# StairMastersPDB.net
KiCad netlist of a schematic drawn in Altium Designer
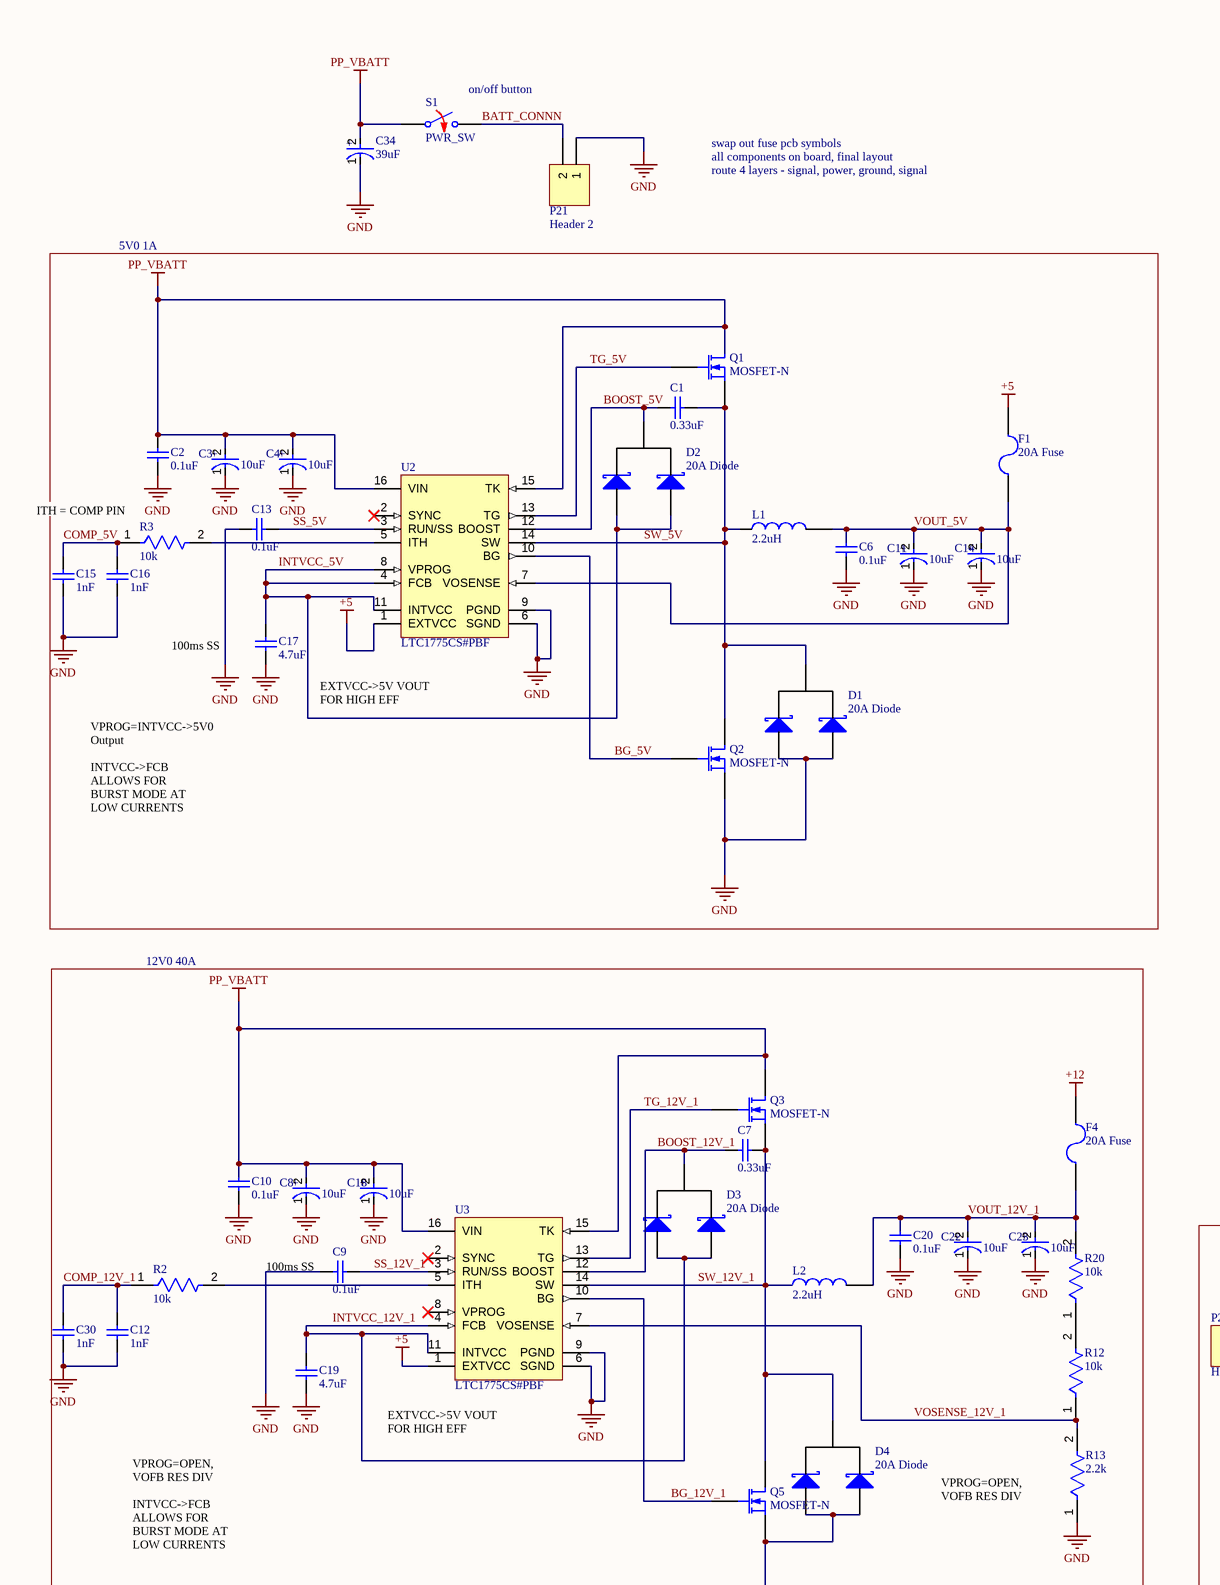
[diagram p0: StairMastersPDB.SchDoc, top left]
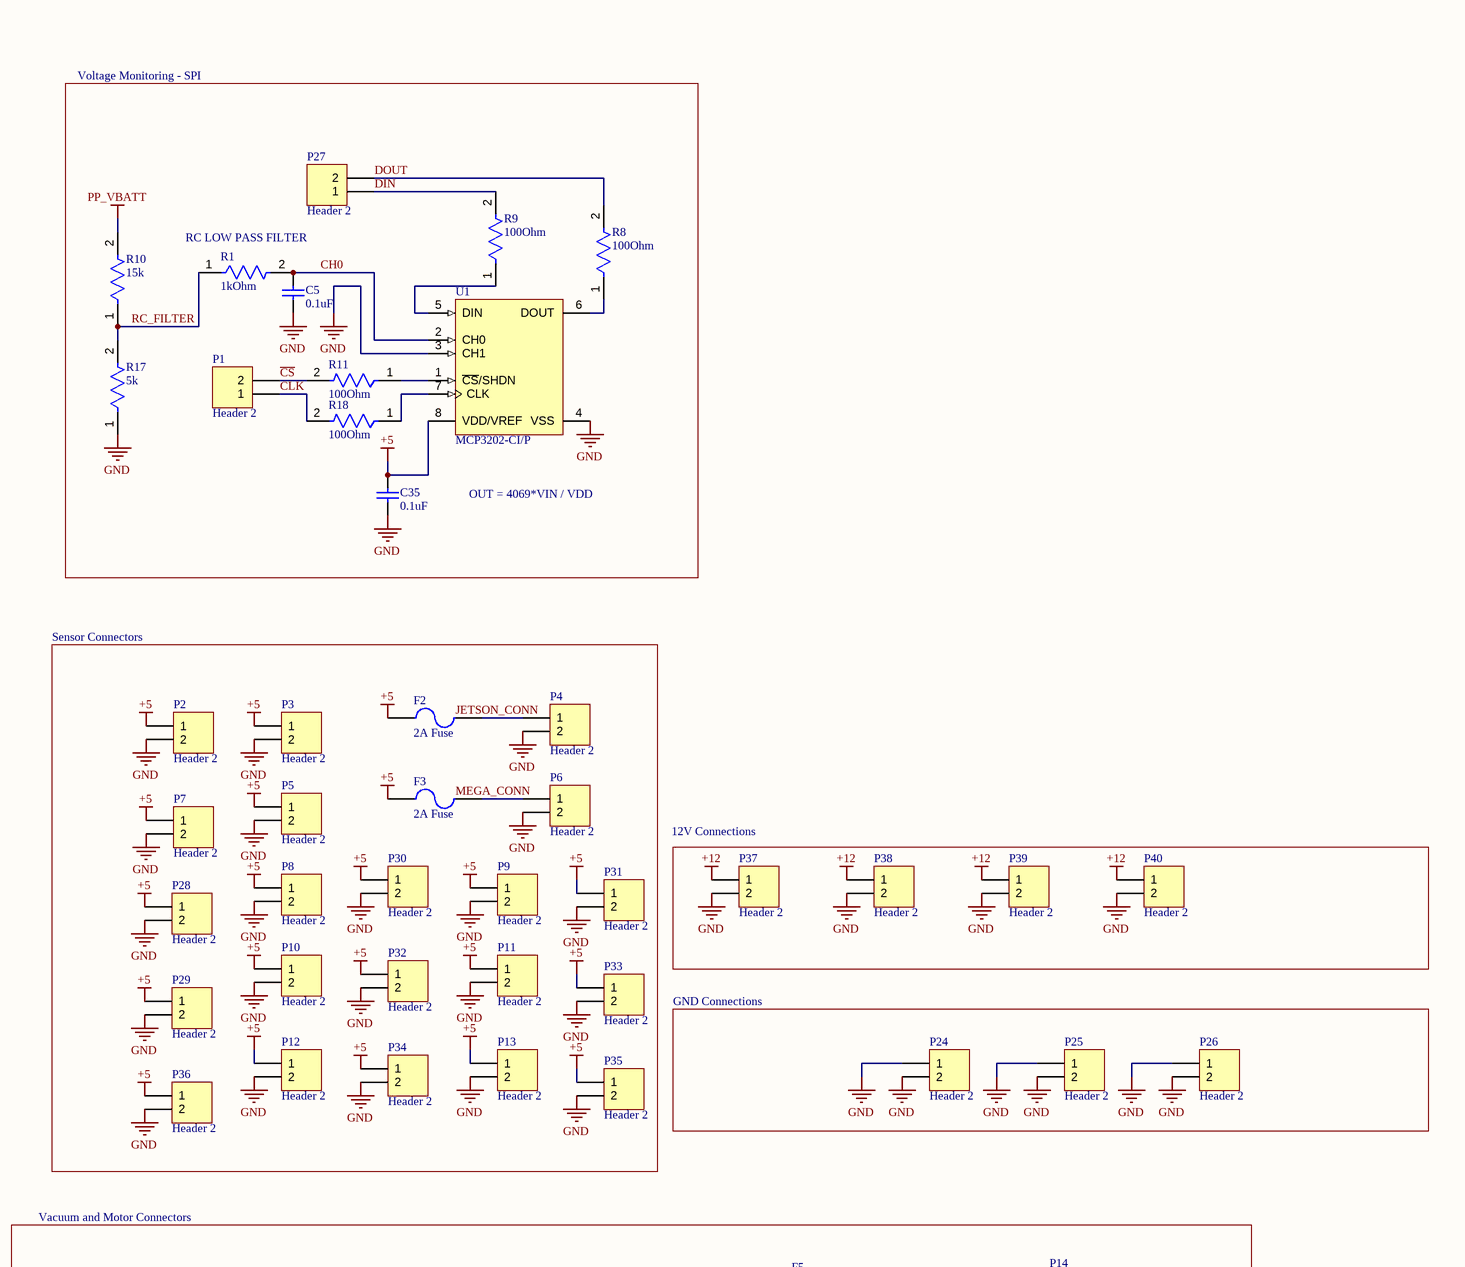
[diagram p1: StairMastersPDB.SchDoc, top right]
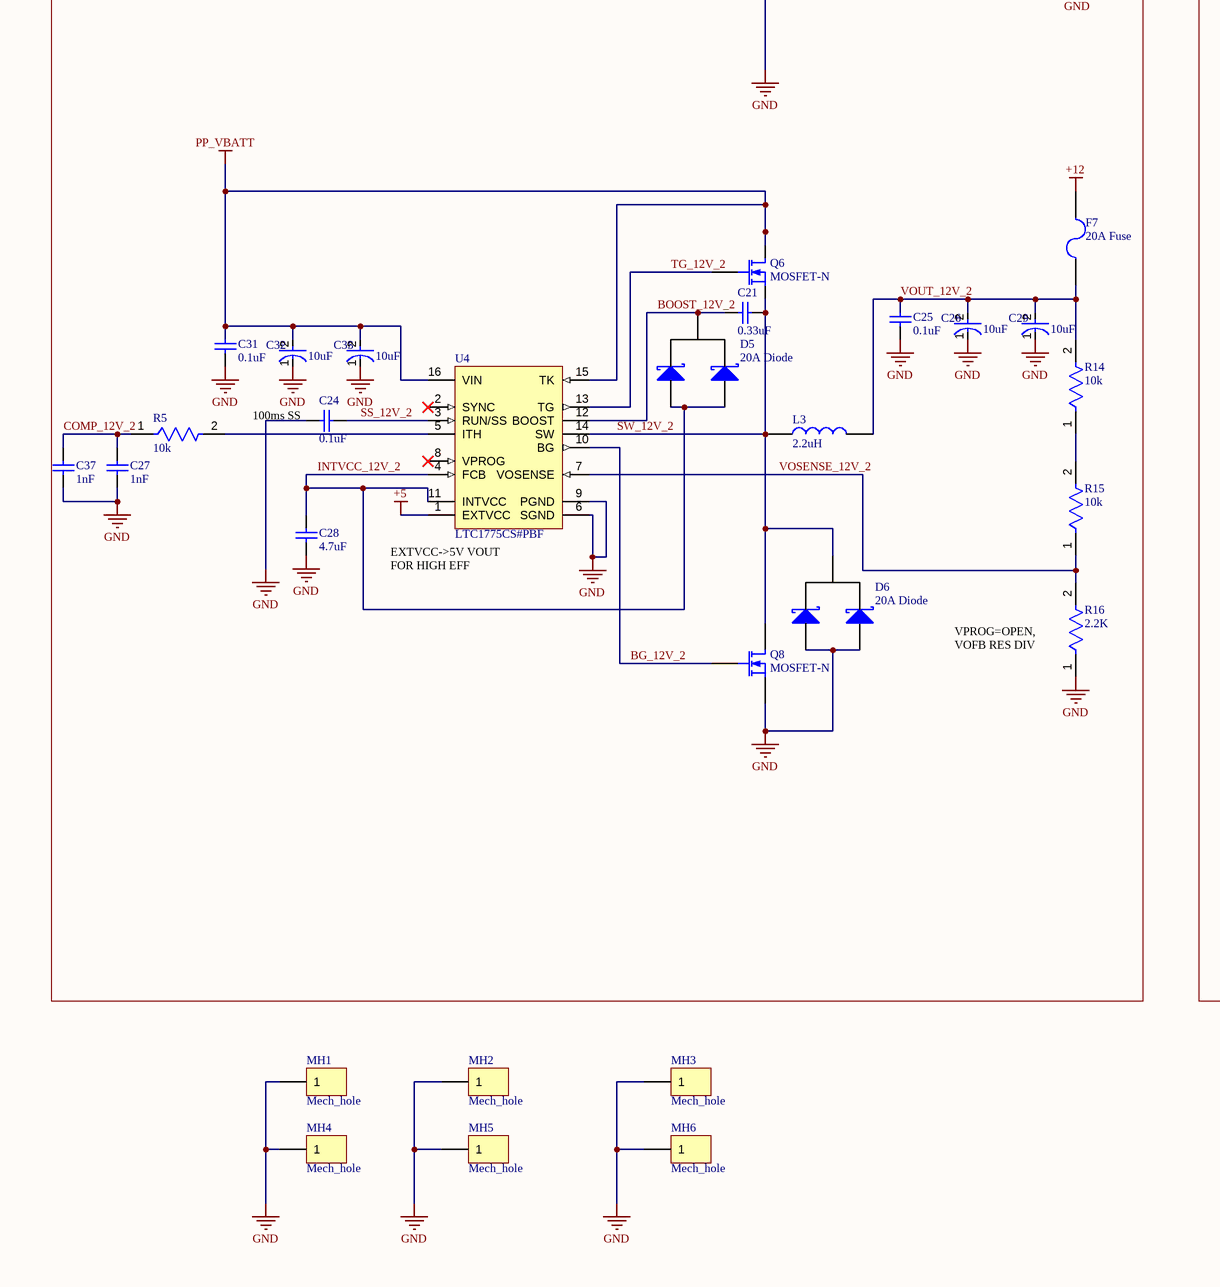
[diagram p2: StairMastersPDB.SchDoc, bottom left]
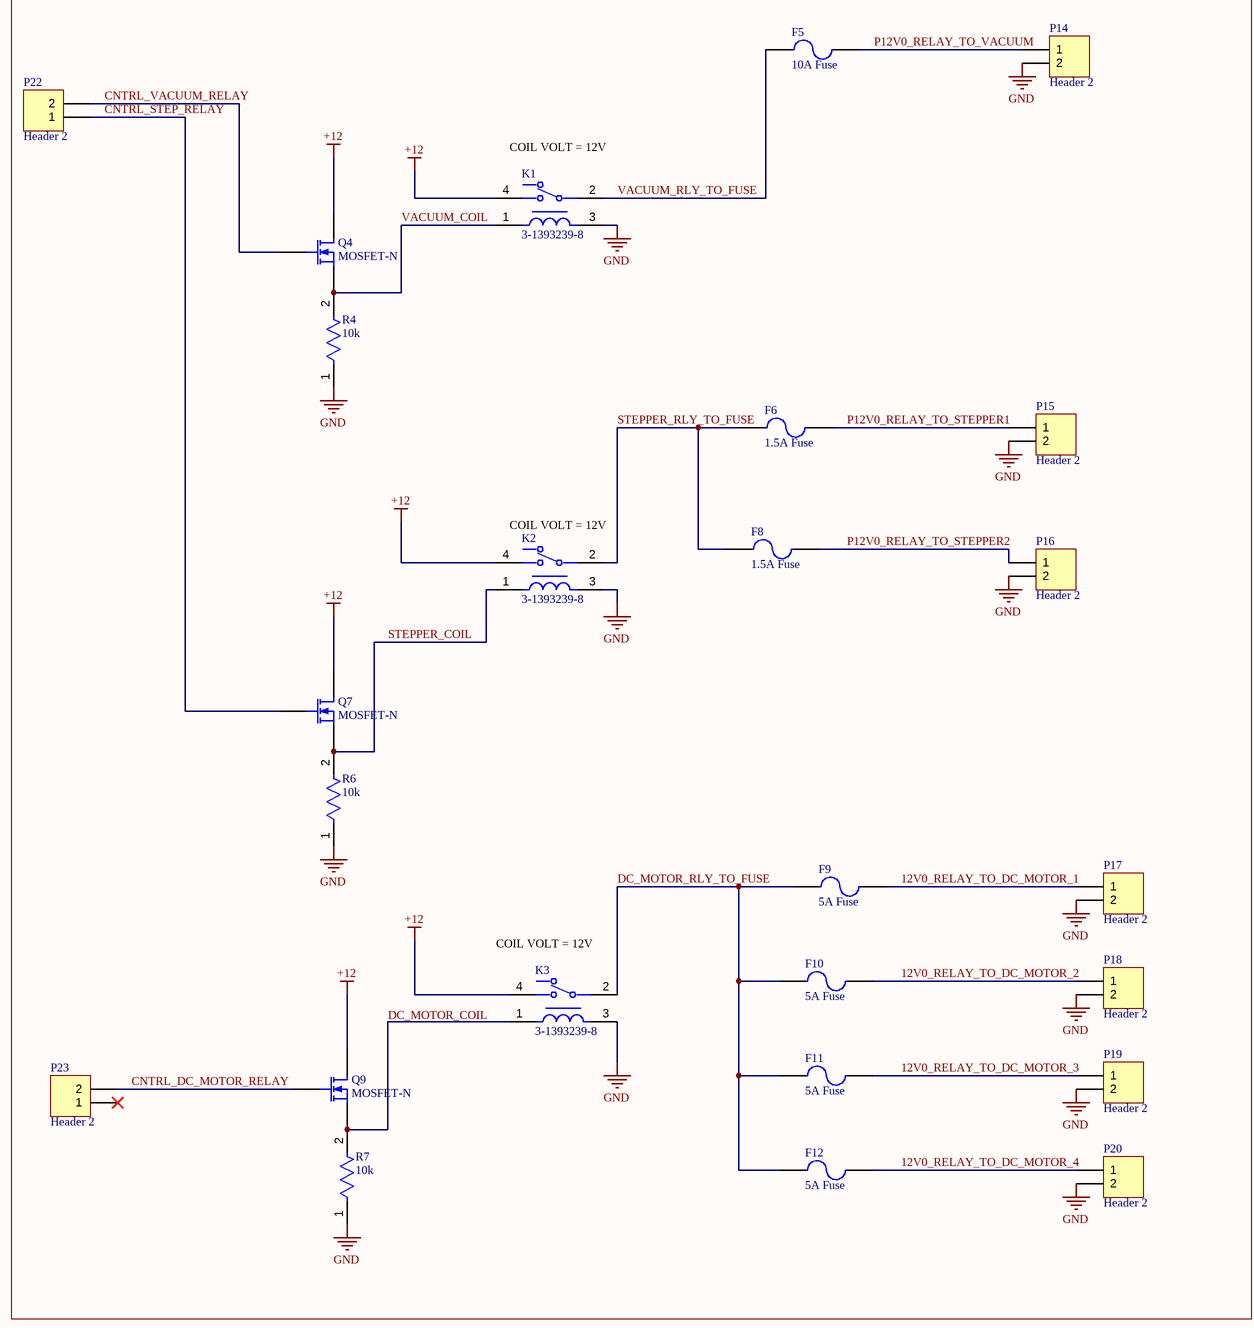
[diagram p3: StairMastersPDB.SchDoc, bottom right]

(export (version "E")
  (design (tool "Eeschema 10.0.6"))
  (components
    (comp (ref "C1")
      (value "0.33uF")
      (footprint "VISH-K104K15X7RF5TL2")
      (description "Ceramic Capacitor, 100 nF, +/- 10%, 50 V, -55 to 125 degC, 2-Pin THD, RoHS, Tape and Reel")
      (fields (field (name "MANUFACTURER") "Vishay") (field (name "TOLERANCE") "±10%"))
      (libsource (lib "Altium Content Vault") (part "CAP-NP-2"))
    )
    (comp (ref "C2")
      (value "0.1uF")
      (footprint "VISH-K104K15X7RF5TL2")
      (description "Ceramic Capacitor, 100 nF, +/- 10%, 50 V, -55 to 125 degC, 2-Pin THD, RoHS, Tape and Reel")
      (fields (field (name "MANUFACTURER") "Vishay") (field (name "TOLERANCE") "±10%"))
      (libsource (lib "Altium Content Vault") (part "CAP-NP-2"))
    )
    (comp (ref "C3")
      (value "10uF")
      (footprint "FP-RAD-TH-D_5_0_5-L_11_1-MFG")
      (description "Aluminum Electrolytic Capacitors (Radial Lead Type) AEC-Q200 Qualified 22uF ±20% 50V")
      (fields (field (name "TOLERANCE") "20%"))
      (libsource (lib "Altium Content Vault") (part "a00bbbee19879c290e62620ae7e47b1"))
    )
    (comp (ref "C4")
      (value "10uF")
      (footprint "FP-RAD-TH-D_5_0_5-L_11_1-MFG")
      (description "Aluminum Electrolytic Capacitors (Radial Lead Type) AEC-Q200 Qualified 22uF ±20% 50V")
      (fields (field (name "TOLERANCE") "20%"))
      (libsource (lib "Altium Content Vault") (part "a00bbbee19879c290e62620ae7e47b1"))
    )
    (comp (ref "C5")
      (value "0.1uF")
      (footprint "VISH-K104K15X7RF5TL2")
      (description "Ceramic Capacitor, 100 nF, +/- 10%, 50 V, -55 to 125 degC, 2-Pin THD, RoHS, Tape and Reel")
      (fields (field (name "MANUFACTURER") "Vishay") (field (name "TOLERANCE") "±10%"))
      (libsource (lib "Altium Content Vault") (part "CAP-NP-2"))
    )
    (comp (ref "C6")
      (value "0.1uF")
      (footprint "VISH-K104K15X7RF5TL2")
      (description "Ceramic Capacitor, 100 nF, +/- 10%, 50 V, -55 to 125 degC, 2-Pin THD, RoHS, Tape and Reel")
      (fields (field (name "MANUFACTURER") "Vishay") (field (name "TOLERANCE") "±10%"))
      (libsource (lib "Altium Content Vault") (part "CAP-NP-2"))
    )
    (comp (ref "C7")
      (value "0.33uF")
      (footprint "VISH-K104K15X7RF5TL2")
      (description "Ceramic Capacitor, 100 nF, +/- 10%, 50 V, -55 to 125 degC, 2-Pin THD, RoHS, Tape and Reel")
      (fields (field (name "MANUFACTURER") "Vishay") (field (name "TOLERANCE") "±10%"))
      (libsource (lib "Altium Content Vault") (part "CAP-NP-2"))
    )
    (comp (ref "C8")
      (value "10uF")
      (footprint "FP-RAD-TH-D_5_0_5-L_11_1-MFG")
      (description "Aluminum Electrolytic Capacitors (Radial Lead Type) AEC-Q200 Qualified 22uF ±20% 50V")
      (fields (field (name "TOLERANCE") "20%"))
      (libsource (lib "Altium Content Vault") (part "a00bbbee19879c290e62620ae7e47b1"))
    )
    (comp (ref "C9")
      (value "0.1uF")
      (footprint "VISH-K104K15X7RF5TL2")
      (description "Ceramic Capacitor, 100 nF, +/- 10%, 50 V, -55 to 125 degC, 2-Pin THD, RoHS, Tape and Reel")
      (fields (field (name "MANUFACTURER") "Vishay") (field (name "TOLERANCE") "±10%"))
      (libsource (lib "Altium Content Vault") (part "CAP-NP-2"))
    )
    (comp (ref "C10")
      (value "0.1uF")
      (footprint "VISH-K104K15X7RF5TL2")
      (description "Ceramic Capacitor, 100 nF, +/- 10%, 50 V, -55 to 125 degC, 2-Pin THD, RoHS, Tape and Reel")
      (fields (field (name "MANUFACTURER") "Vishay") (field (name "TOLERANCE") "±10%"))
      (libsource (lib "Altium Content Vault") (part "CAP-NP-2"))
    )
    (comp (ref "C11")
      (value "10uF")
      (footprint "FP-RAD-TH-D_5_0_5-L_11_1-MFG")
      (description "Aluminum Electrolytic Capacitors (Radial Lead Type) AEC-Q200 Qualified 22uF ±20% 50V")
      (fields (field (name "TOLERANCE") "20%"))
      (libsource (lib "Altium Content Vault") (part "a00bbbee19879c290e62620ae7e47b1"))
    )
    (comp (ref "C12")
      (value "1nF")
      (footprint "VISH-K104K15X7RF5TL2")
      (description "Ceramic Capacitor, 100 nF, +/- 10%, 50 V, -55 to 125 degC, 2-Pin THD, RoHS, Tape and Reel")
      (fields (field (name "MANUFACTURER") "Vishay") (field (name "TOLERANCE") "±10%"))
      (libsource (lib "Altium Content Vault") (part "CAP-NP-2"))
    )
    (comp (ref "C13")
      (value "0.1uF")
      (footprint "VISH-K104K15X7RF5TL2")
      (description "Ceramic Capacitor, 100 nF, +/- 10%, 50 V, -55 to 125 degC, 2-Pin THD, RoHS, Tape and Reel")
      (fields (field (name "MANUFACTURER") "Vishay") (field (name "TOLERANCE") "±10%"))
      (libsource (lib "Altium Content Vault") (part "CAP-NP-2"))
    )
    (comp (ref "C14")
      (value "10uF")
      (footprint "FP-RAD-TH-D_5_0_5-L_11_1-MFG")
      (description "Aluminum Electrolytic Capacitors (Radial Lead Type) AEC-Q200 Qualified 22uF ±20% 50V")
      (fields (field (name "TOLERANCE") "20%"))
      (libsource (lib "Altium Content Vault") (part "a00bbbee19879c290e62620ae7e47b1"))
    )
    (comp (ref "C15")
      (value "1nF")
      (footprint "VISH-K104K15X7RF5TL2")
      (description "Ceramic Capacitor, 100 nF, +/- 10%, 50 V, -55 to 125 degC, 2-Pin THD, RoHS, Tape and Reel")
      (fields (field (name "MANUFACTURER") "Vishay") (field (name "TOLERANCE") "±10%"))
      (libsource (lib "Altium Content Vault") (part "CAP-NP-2"))
    )
    (comp (ref "C16")
      (value "1nF")
      (footprint "VISH-K104K15X7RF5TL2")
      (description "Ceramic Capacitor, 100 nF, +/- 10%, 50 V, -55 to 125 degC, 2-Pin THD, RoHS, Tape and Reel")
      (fields (field (name "MANUFACTURER") "Vishay") (field (name "TOLERANCE") "±10%"))
      (libsource (lib "Altium Content Vault") (part "CAP-NP-2"))
    )
    (comp (ref "C17")
      (value "4.7uF")
      (footprint "VISH-K104K15X7RF5TL2")
      (description "Ceramic Capacitor, 100 nF, +/- 10%, 50 V, -55 to 125 degC, 2-Pin THD, RoHS, Tape and Reel")
      (fields (field (name "MANUFACTURER") "Vishay") (field (name "TOLERANCE") "±10%"))
      (libsource (lib "Altium Content Vault") (part "CAP-NP-2"))
    )
    (comp (ref "C18")
      (value "10uF")
      (footprint "FP-RAD-TH-D_5_0_5-L_11_1-MFG")
      (description "Aluminum Electrolytic Capacitors (Radial Lead Type) AEC-Q200 Qualified 22uF ±20% 50V")
      (fields (field (name "TOLERANCE") "20%"))
      (libsource (lib "Altium Content Vault") (part "a00bbbee19879c290e62620ae7e47b1"))
    )
    (comp (ref "C19")
      (value "4.7uF")
      (footprint "VISH-K104K15X7RF5TL2")
      (description "Ceramic Capacitor, 100 nF, +/- 10%, 50 V, -55 to 125 degC, 2-Pin THD, RoHS, Tape and Reel")
      (fields (field (name "MANUFACTURER") "Vishay") (field (name "TOLERANCE") "±10%"))
      (libsource (lib "Altium Content Vault") (part "CAP-NP-2"))
    )
    (comp (ref "C20")
      (value "0.1uF")
      (footprint "VISH-K104K15X7RF5TL2")
      (description "Ceramic Capacitor, 100 nF, +/- 10%, 50 V, -55 to 125 degC, 2-Pin THD, RoHS, Tape and Reel")
      (fields (field (name "MANUFACTURER") "Vishay") (field (name "TOLERANCE") "±10%"))
      (libsource (lib "Altium Content Vault") (part "CAP-NP-2"))
    )
    (comp (ref "C21")
      (value "0.33uF")
      (footprint "VISH-K104K15X7RF5TL2")
      (description "Ceramic Capacitor, 100 nF, +/- 10%, 50 V, -55 to 125 degC, 2-Pin THD, RoHS, Tape and Reel")
      (fields (field (name "MANUFACTURER") "Vishay") (field (name "TOLERANCE") "±10%"))
      (libsource (lib "Altium Content Vault") (part "CAP-NP-2"))
    )
    (comp (ref "C22")
      (value "10uF")
      (footprint "FP-RAD-TH-D_5_0_5-L_11_1-MFG")
      (description "Aluminum Electrolytic Capacitors (Radial Lead Type) AEC-Q200 Qualified 22uF ±20% 50V")
      (fields (field (name "TOLERANCE") "20%"))
      (libsource (lib "Altium Content Vault") (part "a00bbbee19879c290e62620ae7e47b1"))
    )
    (comp (ref "C23")
      (value "10uF")
      (footprint "FP-RAD-TH-D_5_0_5-L_11_1-MFG")
      (description "Aluminum Electrolytic Capacitors (Radial Lead Type) AEC-Q200 Qualified 22uF ±20% 50V")
      (fields (field (name "TOLERANCE") "20%"))
      (libsource (lib "Altium Content Vault") (part "a00bbbee19879c290e62620ae7e47b1"))
    )
    (comp (ref "C24")
      (value "0.1uF")
      (footprint "VISH-K104K15X7RF5TL2")
      (description "Ceramic Capacitor, 100 nF, +/- 10%, 50 V, -55 to 125 degC, 2-Pin THD, RoHS, Tape and Reel")
      (fields (field (name "MANUFACTURER") "Vishay") (field (name "TOLERANCE") "±10%"))
      (libsource (lib "Altium Content Vault") (part "CAP-NP-2"))
    )
    (comp (ref "C25")
      (value "0.1uF")
      (footprint "VISH-K104K15X7RF5TL2")
      (description "Ceramic Capacitor, 100 nF, +/- 10%, 50 V, -55 to 125 degC, 2-Pin THD, RoHS, Tape and Reel")
      (fields (field (name "MANUFACTURER") "Vishay") (field (name "TOLERANCE") "±10%"))
      (libsource (lib "Altium Content Vault") (part "CAP-NP-2"))
    )
    (comp (ref "C26")
      (value "10uF")
      (footprint "FP-RAD-TH-D_5_0_5-L_11_1-MFG")
      (description "Aluminum Electrolytic Capacitors (Radial Lead Type) AEC-Q200 Qualified 22uF ±20% 50V")
      (fields (field (name "TOLERANCE") "20%"))
      (libsource (lib "Altium Content Vault") (part "a00bbbee19879c290e62620ae7e47b1"))
    )
    (comp (ref "C27")
      (value "1nF")
      (footprint "VISH-K104K15X7RF5TL2")
      (description "Ceramic Capacitor, 100 nF, +/- 10%, 50 V, -55 to 125 degC, 2-Pin THD, RoHS, Tape and Reel")
      (fields (field (name "MANUFACTURER") "Vishay") (field (name "TOLERANCE") "±10%"))
      (libsource (lib "Altium Content Vault") (part "CAP-NP-2"))
    )
    (comp (ref "C28")
      (value "4.7uF")
      (footprint "VISH-K104K15X7RF5TL2")
      (description "Ceramic Capacitor, 100 nF, +/- 10%, 50 V, -55 to 125 degC, 2-Pin THD, RoHS, Tape and Reel")
      (fields (field (name "MANUFACTURER") "Vishay") (field (name "TOLERANCE") "±10%"))
      (libsource (lib "Altium Content Vault") (part "CAP-NP-2"))
    )
    (comp (ref "C29")
      (value "10uF")
      (footprint "FP-RAD-TH-D_5_0_5-L_11_1-MFG")
      (description "Aluminum Electrolytic Capacitors (Radial Lead Type) AEC-Q200 Qualified 22uF ±20% 50V")
      (fields (field (name "TOLERANCE") "20%"))
      (libsource (lib "Altium Content Vault") (part "a00bbbee19879c290e62620ae7e47b1"))
    )
    (comp (ref "C30")
      (value "1nF")
      (footprint "VISH-K104K15X7RF5TL2")
      (description "Ceramic Capacitor, 100 nF, +/- 10%, 50 V, -55 to 125 degC, 2-Pin THD, RoHS, Tape and Reel")
      (fields (field (name "MANUFACTURER") "Vishay") (field (name "TOLERANCE") "±10%"))
      (libsource (lib "Altium Content Vault") (part "CAP-NP-2"))
    )
    (comp (ref "C31")
      (value "0.1uF")
      (footprint "VISH-K104K15X7RF5TL2")
      (description "Ceramic Capacitor, 100 nF, +/- 10%, 50 V, -55 to 125 degC, 2-Pin THD, RoHS, Tape and Reel")
      (fields (field (name "MANUFACTURER") "Vishay") (field (name "TOLERANCE") "±10%"))
      (libsource (lib "Altium Content Vault") (part "CAP-NP-2"))
    )
    (comp (ref "C32")
      (value "10uF")
      (footprint "FP-RAD-TH-D_5_0_5-L_11_1-MFG")
      (description "Aluminum Electrolytic Capacitors (Radial Lead Type) AEC-Q200 Qualified 22uF ±20% 50V")
      (fields (field (name "TOLERANCE") "20%"))
      (libsource (lib "Altium Content Vault") (part "a00bbbee19879c290e62620ae7e47b1"))
    )
    (comp (ref "C33")
      (value "10uF")
      (footprint "FP-RAD-TH-D_5_0_5-L_11_1-MFG")
      (description "Aluminum Electrolytic Capacitors (Radial Lead Type) AEC-Q200 Qualified 22uF ±20% 50V")
      (fields (field (name "TOLERANCE") "20%"))
      (libsource (lib "Altium Content Vault") (part "a00bbbee19879c290e62620ae7e47b1"))
    )
    (comp (ref "C34")
      (value "39uF")
      (footprint "polarized_radial_cap_TH")
      (description "Cap Aluminum 39uF 25V 20% (6.3 X 7mm) Radial 5mm 200mA 1000 hr 105C Ammo Pack")
      (fields
        (field (name "MANUFACTURER") "Panasonic")
        (field (name "MANUFACTURER PART NUMBER") "EEA-FC1E390B")
      )
      (libsource (lib "StairMastersPDB") (part "39uF capacitor"))
    )
    (comp (ref "C35")
      (value "0.1uF")
      (footprint "VISH-K104K15X7RF5TL2")
      (description "Ceramic Capacitor, 100 nF, +/- 10%, 50 V, -55 to 125 degC, 2-Pin THD, RoHS, Tape and Reel")
      (fields (field (name "MANUFACTURER") "Vishay") (field (name "TOLERANCE") "±10%"))
      (libsource (lib "Altium Content Vault") (part "CAP-NP-2"))
    )
    (comp (ref "C37")
      (value "1nF")
      (footprint "VISH-K104K15X7RF5TL2")
      (description "Ceramic Capacitor, 100 nF, +/- 10%, 50 V, -55 to 125 degC, 2-Pin THD, RoHS, Tape and Reel")
      (fields (field (name "MANUFACTURER") "Vishay") (field (name "TOLERANCE") "±10%"))
      (libsource (lib "Altium Content Vault") (part "CAP-NP-2"))
    )
    (comp (ref "D1")
      (value "20A Diode")
      (footprint "DIODE-3-TH")
      (fields (field (name "MANUFACTURER") "Rohm") (field (name "MANUFACTURER PART NUMBER") "RB215T-90NZC9"))
      (libsource (lib "StairMastersPDB") (part "20A Diode"))
    )
    (comp (ref "D2")
      (value "20A Diode")
      (footprint "DIODE-3-TH")
      (fields (field (name "MANUFACTURER") "Rohm") (field (name "MANUFACTURER PART NUMBER") "RB215T-90NZC9"))
      (libsource (lib "StairMastersPDB") (part "20A Diode"))
    )
    (comp (ref "D3")
      (value "20A Diode")
      (footprint "DIODE-3-TH")
      (fields (field (name "MANUFACTURER") "Rohm") (field (name "MANUFACTURER PART NUMBER") "RB215T-90NZC9"))
      (libsource (lib "StairMastersPDB") (part "20A Diode"))
    )
    (comp (ref "D4")
      (value "20A Diode")
      (footprint "DIODE-3-TH")
      (fields (field (name "MANUFACTURER") "Rohm") (field (name "MANUFACTURER PART NUMBER") "RB215T-90NZC9"))
      (libsource (lib "StairMastersPDB") (part "20A Diode"))
    )
    (comp (ref "D5")
      (value "20A Diode")
      (footprint "DIODE-3-TH")
      (fields (field (name "MANUFACTURER") "Rohm") (field (name "MANUFACTURER PART NUMBER") "RB215T-90NZC9"))
      (libsource (lib "StairMastersPDB") (part "20A Diode"))
    )
    (comp (ref "D6")
      (value "20A Diode")
      (footprint "DIODE-3-TH")
      (fields (field (name "MANUFACTURER") "Rohm") (field (name "MANUFACTURER PART NUMBER") "RB215T-90NZC9"))
      (libsource (lib "StairMastersPDB") (part "20A Diode"))
    )
    (comp (ref "F1")
      (value "20A Fuse")
      (footprint "TH_RESISTOR")
      (description "Electric Fuse, Fast Blow, 20A, 1000A (IR), 3AB")
      (fields
        (field (name "MANUFACTURER") "Littelfuse")
        (field (name "MANUFACTURER PART NUMBER") "0314020.MX52LEP")
      )
      (libsource (lib "StairMastersPDB") (part "20A Fuse"))
    )
    (comp (ref "F2")
      (value "2A Fuse")
      (footprint "TH_RESISTOR")
      (description "Fuse Subminiature Very Fast Acting 2A 125V Axial 2.8 X 7.11mm Ceramic T/R")
      (fields
        (field (name "MANUFACTURER") "Littelfuse")
        (field (name "MANUFACTURER PART NUMBER") "0251002.MRT1L")
      )
      (libsource (lib "StairMastersPDB") (part "2A Fuse"))
    )
    (comp (ref "F3")
      (value "2A Fuse")
      (footprint "TH_RESISTOR")
      (description "Fuse Subminiature Very Fast Acting 2A 125V Axial 2.8 X 7.11mm Ceramic T/R")
      (fields
        (field (name "MANUFACTURER") "Littelfuse")
        (field (name "MANUFACTURER PART NUMBER") "0251002.MRT1L")
      )
      (libsource (lib "StairMastersPDB") (part "2A Fuse"))
    )
    (comp (ref "F4")
      (value "20A Fuse")
      (footprint "TH_RESISTOR")
      (description "Electric Fuse, Fast Blow, 20A, 1000A (IR), 3AB")
      (fields
        (field (name "MANUFACTURER") "Littelfuse")
        (field (name "MANUFACTURER PART NUMBER") "0314020.MX52LEP")
      )
      (libsource (lib "StairMastersPDB") (part "20A Fuse"))
    )
    (comp (ref "F5")
      (value "10A Fuse")
      (footprint "TH_RESISTOR")
      (description "Fuse Subminiature Very Fast Acting 10A 125V Axial 2.8 X 7.11mm Ceramic Ammo Pack")
      (fields
        (field (name "MANUFACTURER") "Littelfuse")
        (field (name "MANUFACTURER PART NUMBER") "0251010.HAT1L")
      )
      (libsource (lib "StairMastersPDB") (part "10A Fuse"))
    )
    (comp (ref "F6")
      (value "1.5A Fuse")
      (footprint "TH_RESISTOR")
      (description "Fuse Subminiature Very Fast Acting 1.5A 125V Axial 2.8 X 7.11mm Ceramic T/R")
      (fields
        (field (name "MANUFACTURER") "Littelfuse")
        (field (name "MANUFACTURER PART NUMBER") "025101.5MRT1L")
      )
      (libsource (lib "StairMastersPDB") (part "1.5A Fuse"))
    )
    (comp (ref "F7")
      (value "20A Fuse")
      (footprint "TH_RESISTOR")
      (description "Electric Fuse, Fast Blow, 20A, 1000A (IR), 3AB")
      (fields
        (field (name "MANUFACTURER") "Littelfuse")
        (field (name "MANUFACTURER PART NUMBER") "0314020.MX52LEP")
      )
      (libsource (lib "StairMastersPDB") (part "20A Fuse"))
    )
    (comp (ref "F8")
      (value "1.5A Fuse")
      (footprint "TH_RESISTOR")
      (description "Fuse Subminiature Very Fast Acting 1.5A 125V Axial 2.8 X 7.11mm Ceramic T/R")
      (fields
        (field (name "MANUFACTURER") "Littelfuse")
        (field (name "MANUFACTURER PART NUMBER") "025101.5MRT1L")
      )
      (libsource (lib "StairMastersPDB") (part "1.5A Fuse"))
    )
    (comp (ref "F9")
      (value "5A Fuse")
      (footprint "TH_RESISTOR")
      (description "Electric Fuse, Very Fast Blow, 5A, 125VAC, 125VDC, 50A (IR), Through Hole")
      (fields
        (field (name "MANUFACTURER") "Littelfuse")
        (field (name "MANUFACTURER PART NUMBER") "0251005.NAT1L")
      )
      (libsource (lib "StairMastersPDB") (part "5A Fuse"))
    )
    (comp (ref "F10")
      (value "5A Fuse")
      (footprint "TH_RESISTOR")
      (description "Electric Fuse, Very Fast Blow, 5A, 125VAC, 125VDC, 50A (IR), Through Hole")
      (fields
        (field (name "MANUFACTURER") "Littelfuse")
        (field (name "MANUFACTURER PART NUMBER") "0251005.NAT1L")
      )
      (libsource (lib "StairMastersPDB") (part "5A Fuse"))
    )
    (comp (ref "F11")
      (value "5A Fuse")
      (footprint "TH_RESISTOR")
      (description "Electric Fuse, Very Fast Blow, 5A, 125VAC, 125VDC, 50A (IR), Through Hole")
      (fields
        (field (name "MANUFACTURER") "Littelfuse")
        (field (name "MANUFACTURER PART NUMBER") "0251005.NAT1L")
      )
      (libsource (lib "StairMastersPDB") (part "5A Fuse"))
    )
    (comp (ref "F12")
      (value "5A Fuse")
      (footprint "TH_RESISTOR")
      (description "Electric Fuse, Very Fast Blow, 5A, 125VAC, 125VDC, 50A (IR), Through Hole")
      (fields
        (field (name "MANUFACTURER") "Littelfuse")
        (field (name "MANUFACTURER PART NUMBER") "0251005.NAT1L")
      )
      (libsource (lib "StairMastersPDB") (part "5A Fuse"))
    )
    (comp (ref "K1")
      (value "3-1393239-8")
      (footprint "PR12-12V-360-1A")
      (description "RELAY GEN PURPOSE SPDT 10A 12V")
      (fields
        (field (name "MANUFACTURER") "TE")
        (field (name "OCTOPART") "https://octopart.com/3-1393239-8-te+connectivity-40497687")
      )
      (libsource (lib "StairMastersPDB") (part "PR12-12V-360-1A"))
    )
    (comp (ref "K2")
      (value "3-1393239-8")
      (footprint "PR12-12V-360-1A")
      (description "RELAY GEN PURPOSE SPDT 10A 12V")
      (fields
        (field (name "MANUFACTURER") "TE")
        (field (name "OCTOPART") "https://octopart.com/3-1393239-8-te+connectivity-40497687")
      )
      (libsource (lib "StairMastersPDB") (part "PR12-12V-360-1A"))
    )
    (comp (ref "K3")
      (value "3-1393239-8")
      (footprint "PR12-12V-360-1A")
      (description "RELAY GEN PURPOSE SPDT 10A 12V")
      (fields
        (field (name "MANUFACTURER") "TE")
        (field (name "OCTOPART") "https://octopart.com/3-1393239-8-te+connectivity-40497687")
      )
      (libsource (lib "StairMastersPDB") (part "PR12-12V-360-1A"))
    )
    (comp (ref "L1")
      (value "2.2uH")
      (footprint "SRP1265WA2R2M")
      (fields
        (field (name "MOUSER PART NUMBER") "652-SRP1265WA-2R2M")
        (field (name "MANUFACTURER_PART_NUMBER") "SRP1265WA-2R2M")
      )
      (libsource (lib "StairMastersPDB") (part "SRP1265WA-2R2M_1"))
    )
    (comp (ref "L2")
      (value "2.2uH")
      (footprint "SRP1265WA2R2M")
      (fields
        (field (name "MOUSER PART NUMBER") "652-SRP1265WA-2R2M")
        (field (name "MANUFACTURER_PART_NUMBER") "SRP1265WA-2R2M")
      )
      (libsource (lib "StairMastersPDB") (part "SRP1265WA-2R2M_1"))
    )
    (comp (ref "L3")
      (value "2.2uH")
      (footprint "SRP1265WA2R2M")
      (fields
        (field (name "MOUSER PART NUMBER") "652-SRP1265WA-2R2M")
        (field (name "MANUFACTURER_PART_NUMBER") "SRP1265WA-2R2M")
      )
      (libsource (lib "StairMastersPDB") (part "SRP1265WA-2R2M_1"))
    )
    (comp (ref "MH1")
      (value "Mech_hole")
      (footprint "Mounting Hole")
      (libsource (lib "StairMastersPDB") (part "Mech_hole"))
    )
    (comp (ref "MH2")
      (value "Mech_hole")
      (footprint "Mounting Hole")
      (libsource (lib "StairMastersPDB") (part "Mech_hole"))
    )
    (comp (ref "MH3")
      (value "Mech_hole")
      (footprint "Mounting Hole")
      (libsource (lib "StairMastersPDB") (part "Mech_hole"))
    )
    (comp (ref "MH4")
      (value "Mech_hole")
      (footprint "Mounting Hole")
      (libsource (lib "StairMastersPDB") (part "Mech_hole"))
    )
    (comp (ref "MH5")
      (value "Mech_hole")
      (footprint "Mounting Hole")
      (libsource (lib "StairMastersPDB") (part "Mech_hole"))
    )
    (comp (ref "MH6")
      (value "Mech_hole")
      (footprint "Mounting Hole")
      (libsource (lib "StairMastersPDB") (part "Mech_hole"))
    )
    (comp (ref "P1")
      (value "Header 2")
      (footprint "HDR1X2")
      (description "Header, 2-Pin")
      (fields (field (name "PUBLISHER") "Altium Limited"))
      (libsource (lib "") (part "Header 2_1"))
    )
    (comp (ref "P2")
      (value "Header 2")
      (footprint "HDR1X2")
      (description "Header, 2-Pin")
      (fields (field (name "PUBLISHER") "Altium Limited"))
      (libsource (lib "Miscellaneous Connectors") (part "Header 2"))
    )
    (comp (ref "P3")
      (value "Header 2")
      (footprint "HDR1X2")
      (description "Header, 2-Pin")
      (fields (field (name "PUBLISHER") "Altium Limited"))
      (libsource (lib "Miscellaneous Connectors") (part "Header 2"))
    )
    (comp (ref "P4")
      (value "Header 2")
      (footprint "HDR1X2")
      (description "Header, 2-Pin")
      (fields (field (name "PUBLISHER") "Altium Limited"))
      (libsource (lib "Miscellaneous Connectors") (part "Header 2"))
    )
    (comp (ref "P5")
      (value "Header 2")
      (footprint "HDR1X2")
      (description "Header, 2-Pin")
      (fields (field (name "PUBLISHER") "Altium Limited"))
      (libsource (lib "Miscellaneous Connectors") (part "Header 2"))
    )
    (comp (ref "P6")
      (value "Header 2")
      (footprint "HDR1X2")
      (description "Header, 2-Pin")
      (fields (field (name "PUBLISHER") "Altium Limited"))
      (libsource (lib "Miscellaneous Connectors") (part "Header 2"))
    )
    (comp (ref "P7")
      (value "Header 2")
      (footprint "HDR1X2")
      (description "Header, 2-Pin")
      (fields (field (name "PUBLISHER") "Altium Limited"))
      (libsource (lib "Miscellaneous Connectors") (part "Header 2"))
    )
    (comp (ref "P8")
      (value "Header 2")
      (footprint "HDR1X2")
      (description "Header, 2-Pin")
      (fields (field (name "PUBLISHER") "Altium Limited"))
      (libsource (lib "Miscellaneous Connectors") (part "Header 2"))
    )
    (comp (ref "P9")
      (value "Header 2")
      (footprint "HDR1X2")
      (description "Header, 2-Pin")
      (fields (field (name "PUBLISHER") "Altium Limited"))
      (libsource (lib "Miscellaneous Connectors") (part "Header 2"))
    )
    (comp (ref "P10")
      (value "Header 2")
      (footprint "HDR1X2")
      (description "Header, 2-Pin")
      (fields (field (name "PUBLISHER") "Altium Limited"))
      (libsource (lib "Miscellaneous Connectors") (part "Header 2"))
    )
    (comp (ref "P11")
      (value "Header 2")
      (footprint "HDR1X2")
      (description "Header, 2-Pin")
      (fields (field (name "PUBLISHER") "Altium Limited"))
      (libsource (lib "Miscellaneous Connectors") (part "Header 2"))
    )
    (comp (ref "P12")
      (value "Header 2")
      (footprint "HDR1X2")
      (description "Header, 2-Pin")
      (fields (field (name "PUBLISHER") "Altium Limited"))
      (libsource (lib "Miscellaneous Connectors") (part "Header 2"))
    )
    (comp (ref "P13")
      (value "Header 2")
      (footprint "HDR1X2")
      (description "Header, 2-Pin")
      (fields (field (name "PUBLISHER") "Altium Limited"))
      (libsource (lib "Miscellaneous Connectors") (part "Header 2"))
    )
    (comp (ref "P14")
      (value "Header 2")
      (footprint "HDR1X2")
      (description "Header, 2-Pin")
      (fields (field (name "PUBLISHER") "Altium Limited"))
      (libsource (lib "Miscellaneous Connectors") (part "Header 2"))
    )
    (comp (ref "P15")
      (value "Header 2")
      (footprint "HDR1X2")
      (description "Header, 2-Pin")
      (fields (field (name "PUBLISHER") "Altium Limited"))
      (libsource (lib "Miscellaneous Connectors") (part "Header 2"))
    )
    (comp (ref "P16")
      (value "Header 2")
      (footprint "HDR1X2")
      (description "Header, 2-Pin")
      (fields (field (name "PUBLISHER") "Altium Limited"))
      (libsource (lib "Miscellaneous Connectors") (part "Header 2"))
    )
    (comp (ref "P17")
      (value "Header 2")
      (footprint "HDR1X2")
      (description "Header, 2-Pin")
      (fields (field (name "PUBLISHER") "Altium Limited"))
      (libsource (lib "Miscellaneous Connectors") (part "Header 2"))
    )
    (comp (ref "P18")
      (value "Header 2")
      (footprint "HDR1X2")
      (description "Header, 2-Pin")
      (fields (field (name "PUBLISHER") "Altium Limited"))
      (libsource (lib "Miscellaneous Connectors") (part "Header 2"))
    )
    (comp (ref "P19")
      (value "Header 2")
      (footprint "HDR1X2")
      (description "Header, 2-Pin")
      (fields (field (name "PUBLISHER") "Altium Limited"))
      (libsource (lib "Miscellaneous Connectors") (part "Header 2"))
    )
    (comp (ref "P20")
      (value "Header 2")
      (footprint "HDR1X2")
      (description "Header, 2-Pin")
      (fields (field (name "PUBLISHER") "Altium Limited"))
      (libsource (lib "Miscellaneous Connectors") (part "Header 2"))
    )
    (comp (ref "P21")
      (value "Header 2")
      (footprint "PWR_HDR1X2")
      (description "Header, 2-Pin")
      (fields (field (name "PUBLISHER") "Altium Limited"))
      (libsource (lib "StairMastersPDB") (part "PWR_CONN"))
    )
    (comp (ref "P22")
      (value "Header 2")
      (footprint "HDR1X2")
      (description "Header, 2-Pin")
      (fields (field (name "PUBLISHER") "Altium Limited"))
      (libsource (lib "") (part "Header 2_1"))
    )
    (comp (ref "P23")
      (value "Header 2")
      (footprint "HDR1X2")
      (description "Header, 2-Pin")
      (fields (field (name "PUBLISHER") "Altium Limited"))
      (libsource (lib "") (part "Header 2_1"))
    )
    (comp (ref "P24")
      (value "Header 2")
      (footprint "HDR1X2")
      (description "Header, 2-Pin")
      (fields (field (name "PUBLISHER") "Altium Limited"))
      (libsource (lib "Miscellaneous Connectors") (part "Header 2"))
    )
    (comp (ref "P25")
      (value "Header 2")
      (footprint "HDR1X2")
      (description "Header, 2-Pin")
      (fields (field (name "PUBLISHER") "Altium Limited"))
      (libsource (lib "Miscellaneous Connectors") (part "Header 2"))
    )
    (comp (ref "P26")
      (value "Header 2")
      (footprint "HDR1X2")
      (description "Header, 2-Pin")
      (fields (field (name "PUBLISHER") "Altium Limited"))
      (libsource (lib "Miscellaneous Connectors") (part "Header 2"))
    )
    (comp (ref "P27")
      (value "Header 2")
      (footprint "HDR1X2")
      (description "Header, 2-Pin")
      (fields (field (name "PUBLISHER") "Altium Limited"))
      (libsource (lib "") (part "Header 2_1"))
    )
    (comp (ref "P28")
      (value "Header 2")
      (footprint "HDR1X2")
      (description "Header, 2-Pin")
      (fields (field (name "PUBLISHER") "Altium Limited"))
      (libsource (lib "Miscellaneous Connectors") (part "Header 2"))
    )
    (comp (ref "P29")
      (value "Header 2")
      (footprint "HDR1X2")
      (description "Header, 2-Pin")
      (fields (field (name "PUBLISHER") "Altium Limited"))
      (libsource (lib "Miscellaneous Connectors") (part "Header 2"))
    )
    (comp (ref "P30")
      (value "Header 2")
      (footprint "HDR1X2")
      (description "Header, 2-Pin")
      (fields (field (name "PUBLISHER") "Altium Limited"))
      (libsource (lib "Miscellaneous Connectors") (part "Header 2"))
    )
    (comp (ref "P31")
      (value "Header 2")
      (footprint "HDR1X2")
      (description "Header, 2-Pin")
      (fields (field (name "PUBLISHER") "Altium Limited"))
      (libsource (lib "Miscellaneous Connectors") (part "Header 2"))
    )
    (comp (ref "P32")
      (value "Header 2")
      (footprint "HDR1X2")
      (description "Header, 2-Pin")
      (fields (field (name "PUBLISHER") "Altium Limited"))
      (libsource (lib "Miscellaneous Connectors") (part "Header 2"))
    )
    (comp (ref "P33")
      (value "Header 2")
      (footprint "HDR1X2")
      (description "Header, 2-Pin")
      (fields (field (name "PUBLISHER") "Altium Limited"))
      (libsource (lib "Miscellaneous Connectors") (part "Header 2"))
    )
    (comp (ref "P34")
      (value "Header 2")
      (footprint "HDR1X2")
      (description "Header, 2-Pin")
      (fields (field (name "PUBLISHER") "Altium Limited"))
      (libsource (lib "Miscellaneous Connectors") (part "Header 2"))
    )
    (comp (ref "P35")
      (value "Header 2")
      (footprint "HDR1X2")
      (description "Header, 2-Pin")
      (fields (field (name "PUBLISHER") "Altium Limited"))
      (libsource (lib "Miscellaneous Connectors") (part "Header 2"))
    )
    (comp (ref "P36")
      (value "Header 2")
      (footprint "HDR1X2")
      (description "Header, 2-Pin")
      (fields (field (name "PUBLISHER") "Altium Limited"))
      (libsource (lib "Miscellaneous Connectors") (part "Header 2"))
    )
    (comp (ref "P37")
      (value "Header 2")
      (footprint "HDR1X2")
      (description "Header, 2-Pin")
      (fields (field (name "PUBLISHER") "Altium Limited"))
      (libsource (lib "Miscellaneous Connectors") (part "Header 2"))
    )
    (comp (ref "P38")
      (value "Header 2")
      (footprint "HDR1X2")
      (description "Header, 2-Pin")
      (fields (field (name "PUBLISHER") "Altium Limited"))
      (libsource (lib "Miscellaneous Connectors") (part "Header 2"))
    )
    (comp (ref "P39")
      (value "Header 2")
      (footprint "HDR1X2")
      (description "Header, 2-Pin")
      (fields (field (name "PUBLISHER") "Altium Limited"))
      (libsource (lib "Miscellaneous Connectors") (part "Header 2"))
    )
    (comp (ref "P40")
      (value "Header 2")
      (footprint "HDR1X2")
      (description "Header, 2-Pin")
      (fields (field (name "PUBLISHER") "Altium Limited"))
      (libsource (lib "Miscellaneous Connectors") (part "Header 2"))
    )
    (comp (ref "Q1")
      (value "MOSFET-N")
      (footprint "FET-3-TH")
      (description "N-Channel MOSFET")
      (fields (field (name "PUBLISHER") "Altium Limited"))
      (libsource (lib "Miscellaneous Devices") (part "MOSFET-N"))
    )
    (comp (ref "Q2")
      (value "MOSFET-N")
      (footprint "FET-3-TH")
      (description "N-Channel MOSFET")
      (fields (field (name "PUBLISHER") "Altium Limited"))
      (libsource (lib "Miscellaneous Devices") (part "MOSFET-N"))
    )
    (comp (ref "Q3")
      (value "MOSFET-N")
      (footprint "FET-3-TH")
      (description "N-Channel MOSFET")
      (fields (field (name "PUBLISHER") "Altium Limited"))
      (libsource (lib "Miscellaneous Devices") (part "MOSFET-N"))
    )
    (comp (ref "Q4")
      (value "MOSFET-N")
      (footprint "FET-3-TH")
      (description "N-Channel MOSFET")
      (fields (field (name "PUBLISHER") "Altium Limited"))
      (libsource (lib "Miscellaneous Devices") (part "MOSFET-N"))
    )
    (comp (ref "Q5")
      (value "MOSFET-N")
      (footprint "FET-3-TH")
      (description "N-Channel MOSFET")
      (fields (field (name "PUBLISHER") "Altium Limited"))
      (libsource (lib "Miscellaneous Devices") (part "MOSFET-N"))
    )
    (comp (ref "Q6")
      (value "MOSFET-N")
      (footprint "FET-3-TH")
      (description "N-Channel MOSFET")
      (fields (field (name "PUBLISHER") "Altium Limited"))
      (libsource (lib "Miscellaneous Devices") (part "MOSFET-N"))
    )
    (comp (ref "Q7")
      (value "MOSFET-N")
      (footprint "FET-3-TH")
      (description "N-Channel MOSFET")
      (fields (field (name "PUBLISHER") "Altium Limited"))
      (libsource (lib "Miscellaneous Devices") (part "MOSFET-N"))
    )
    (comp (ref "Q8")
      (value "MOSFET-N")
      (footprint "FET-3-TH")
      (description "N-Channel MOSFET")
      (fields (field (name "PUBLISHER") "Altium Limited"))
      (libsource (lib "Miscellaneous Devices") (part "MOSFET-N"))
    )
    (comp (ref "Q9")
      (value "MOSFET-N")
      (footprint "FET-3-TH")
      (description "N-Channel MOSFET")
      (fields (field (name "PUBLISHER") "Altium Limited"))
      (libsource (lib "Miscellaneous Devices") (part "MOSFET-N"))
    )
    (comp (ref "R1")
      (value "1kOhm")
      (footprint "FP-MRS25-MFG")
      (description "RES 1K OHM 0.6W 1% AXIAL")
      (fields (field (name "TOLERANCE") "1%"))
      (libsource (lib "Altium Content Vault") (part "1029c3af85768c4190bb7ad29bc67b5"))
    )
    (comp (ref "R2")
      (value "10k")
      (footprint "FP-MBB0207-MFG")
      (description "RES 10K OHM 0.6W 1% AXIAL")
      (fields (field (name "TOLERANCE") "1%"))
      (libsource (lib "Altium Content Vault") (part "1029c3af85768c4190bb7ad29bc67b5"))
    )
    (comp (ref "R3")
      (value "10k")
      (footprint "FP-MBB0207-MFG")
      (description "RES 10K OHM 0.6W 1% AXIAL")
      (fields (field (name "TOLERANCE") "1%"))
      (libsource (lib "Altium Content Vault") (part "1029c3af85768c4190bb7ad29bc67b5"))
    )
    (comp (ref "R4")
      (value "10k")
      (footprint "FP-MBB0207-MFG")
      (description "RES 10K OHM 0.6W 1% AXIAL")
      (fields (field (name "TOLERANCE") "1%"))
      (libsource (lib "Altium Content Vault") (part "1029c3af85768c4190bb7ad29bc67b5"))
    )
    (comp (ref "R5")
      (value "10k")
      (footprint "FP-MBB0207-MFG")
      (description "RES 10K OHM 0.6W 1% AXIAL")
      (fields (field (name "TOLERANCE") "1%"))
      (libsource (lib "Altium Content Vault") (part "1029c3af85768c4190bb7ad29bc67b5"))
    )
    (comp (ref "R6")
      (value "10k")
      (footprint "FP-MBB0207-MFG")
      (description "RES 10K OHM 0.6W 1% AXIAL")
      (fields (field (name "TOLERANCE") "1%"))
      (libsource (lib "Altium Content Vault") (part "1029c3af85768c4190bb7ad29bc67b5"))
    )
    (comp (ref "R7")
      (value "10k")
      (footprint "FP-MBB0207-MFG")
      (description "RES 10K OHM 0.6W 1% AXIAL")
      (fields (field (name "TOLERANCE") "1%"))
      (libsource (lib "Altium Content Vault") (part "1029c3af85768c4190bb7ad29bc67b5"))
    )
    (comp (ref "R8")
      (value "100Ohm")
      (footprint "FP-MBB0207-MFG")
      (description "RES 10K OHM 0.6W 1% AXIAL")
      (fields (field (name "TOLERANCE") "1%"))
      (libsource (lib "Altium Content Vault") (part "1029c3af85768c4190bb7ad29bc67b5"))
    )
    (comp (ref "R9")
      (value "100Ohm")
      (footprint "FP-MBB0207-MFG")
      (description "RES 10K OHM 0.6W 1% AXIAL")
      (fields (field (name "TOLERANCE") "1%"))
      (libsource (lib "Altium Content Vault") (part "1029c3af85768c4190bb7ad29bc67b5"))
    )
    (comp (ref "R10")
      (value "15k")
      (footprint "FP-MBB0207-MFG")
      (description "RES 10K OHM 0.6W 1% AXIAL")
      (fields (field (name "TOLERANCE") "1%"))
      (libsource (lib "Altium Content Vault") (part "1029c3af85768c4190bb7ad29bc67b5"))
    )
    (comp (ref "R11")
      (value "100Ohm")
      (footprint "FP-MBB0207-MFG")
      (description "RES 10K OHM 0.6W 1% AXIAL")
      (fields (field (name "TOLERANCE") "1%"))
      (libsource (lib "Altium Content Vault") (part "1029c3af85768c4190bb7ad29bc67b5"))
    )
    (comp (ref "R12")
      (value "10k")
      (footprint "FP-MBB0207-MFG")
      (description "Fixed Resistor, Metal Film, 2W, 100000ohm, 500V, 5% +/-Tol, 250ppm/Cel, Through Hole Mount")
      (fields
        (field (name "MANUFACTURER") "Vishay BCcomponents")
        (field (name "MANUFACTURER PART NUMBER") "PR02000201003JA100")
      )
      (libsource (lib "StairMastersPDB") (part "100k Resistor"))
    )
    (comp (ref "R13")
      (value "2.2k")
      (footprint "FP-MBB0207-MFG")
      (description "Fixed Resistor, Metal Film, 0.4W, 11000ohm, 350V, 1% +/-Tol, 50ppm/Cel, Through Hole Mount")
      (fields
        (field (name "MANUFACTURER") "Vishay Semiconductors")
        (field (name "MANUFACTURER PART NUMBER") "MBB02070C1102FC100")
      )
      (libsource (lib "StairMastersPDB") (part "11k Resistor"))
    )
    (comp (ref "R14")
      (value "10k")
      (footprint "FP-MBB0207-MFG")
      (description "Fixed Resistor, Metal Film, 2W, 100000ohm, 500V, 5% +/-Tol, 250ppm/Cel, Through Hole Mount")
      (fields
        (field (name "MANUFACTURER") "Vishay BCcomponents")
        (field (name "MANUFACTURER PART NUMBER") "PR02000201003JA100")
      )
      (libsource (lib "StairMastersPDB") (part "100k Resistor"))
    )
    (comp (ref "R15")
      (value "10k")
      (footprint "FP-MBB0207-MFG")
      (description "Fixed Resistor, Metal Film, 2W, 100000ohm, 500V, 5% +/-Tol, 250ppm/Cel, Through Hole Mount")
      (fields
        (field (name "MANUFACTURER") "Vishay BCcomponents")
        (field (name "MANUFACTURER PART NUMBER") "PR02000201003JA100")
      )
      (libsource (lib "StairMastersPDB") (part "100k Resistor"))
    )
    (comp (ref "R16")
      (value "2.2K")
      (footprint "FP-MBB0207-MFG")
      (description "Fixed Resistor, Metal Film, 0.4W, 11000ohm, 350V, 1% +/-Tol, 50ppm/Cel, Through Hole Mount")
      (fields
        (field (name "MANUFACTURER") "Vishay Semiconductors")
        (field (name "MANUFACTURER PART NUMBER") "MBB02070C1102FC100")
      )
      (libsource (lib "StairMastersPDB") (part "11k Resistor"))
    )
    (comp (ref "R17")
      (value "5k")
      (footprint "FP-MBB0207-MFG")
      (description "RES 10K OHM 0.6W 1% AXIAL")
      (fields (field (name "TOLERANCE") "1%"))
      (libsource (lib "Altium Content Vault") (part "1029c3af85768c4190bb7ad29bc67b5"))
    )
    (comp (ref "R18")
      (value "100Ohm")
      (footprint "FP-MBB0207-MFG")
      (description "RES 10K OHM 0.6W 1% AXIAL")
      (fields (field (name "TOLERANCE") "1%"))
      (libsource (lib "Altium Content Vault") (part "1029c3af85768c4190bb7ad29bc67b5"))
    )
    (comp (ref "R20")
      (value "10k")
      (footprint "FP-MBB0207-MFG")
      (description "Fixed Resistor, Metal Film, 2W, 100000ohm, 500V, 5% +/-Tol, 250ppm/Cel, Through Hole Mount")
      (fields
        (field (name "MANUFACTURER") "Vishay BCcomponents")
        (field (name "MANUFACTURER PART NUMBER") "PR02000201003JA100")
      )
      (libsource (lib "StairMastersPDB") (part "100k Resistor"))
    )
    (comp (ref "S1")
      (value "PWR_SW")
      (footprint "PWR_HDR1X2")
      (libsource (lib "StairMastersPDB") (part "PWR_SW"))
    )
    (comp (ref "U1")
      (value "MCP3202-CI/P")
      (footprint "PDIP300-P8")
      (libsource (lib "Altium Content Vault") (part "CON-ADC-MCP3002-8"))
    )
    (comp (ref "U2")
      (value "LTC1775CS#PBF")
      (footprint "LT-S-16_M")
      (fields (field (name "MANUFACTURER") "Linear Technology"))
      (libsource (lib "Altium Content Vault") (part "LT-LTC1775-X-16"))
    )
    (comp (ref "U3")
      (value "LTC1775CS#PBF")
      (footprint "LT-S-16_M")
      (fields (field (name "MANUFACTURER") "Linear Technology"))
      (libsource (lib "Altium Content Vault") (part "LT-LTC1775-X-16"))
    )
    (comp (ref "U4")
      (value "LTC1775CS#PBF")
      (footprint "LT-S-16_M")
      (fields (field (name "MANUFACTURER") "Linear Technology"))
      (libsource (lib "Altium Content Vault") (part "LT-LTC1775-X-16"))
    )
  )
  (nets
    (net (code "1") (name "+5") (class "Default")
      (node (ref "C35") (pin "2") (pinfunction "2_2") (pintype "passive"))
      (node (ref "F1") (pin "2") (pinfunction "2_2") (pintype "passive"))
      (node (ref "F2") (pin "1") (pinfunction "1_1") (pintype "passive"))
      (node (ref "F3") (pin "1") (pinfunction "1_1") (pintype "passive"))
      (node (ref "P10") (pin "1") (pinfunction "1_1") (pintype "passive"))
      (node (ref "P11") (pin "1") (pinfunction "1_1") (pintype "passive"))
      (node (ref "P12") (pin "1") (pinfunction "1_1") (pintype "passive"))
      (node (ref "P13") (pin "1") (pinfunction "1_1") (pintype "passive"))
      (node (ref "P2") (pin "1") (pinfunction "1_1") (pintype "passive"))
      (node (ref "P28") (pin "1") (pinfunction "1_1") (pintype "passive"))
      (node (ref "P29") (pin "1") (pinfunction "1_1") (pintype "passive"))
      (node (ref "P3") (pin "1") (pinfunction "1_1") (pintype "passive"))
      (node (ref "P30") (pin "1") (pinfunction "1_1") (pintype "passive"))
      (node (ref "P31") (pin "1") (pinfunction "1_1") (pintype "passive"))
      (node (ref "P32") (pin "1") (pinfunction "1_1") (pintype "passive"))
      (node (ref "P33") (pin "1") (pinfunction "1_1") (pintype "passive"))
      (node (ref "P34") (pin "1") (pinfunction "1_1") (pintype "passive"))
      (node (ref "P35") (pin "1") (pinfunction "1_1") (pintype "passive"))
      (node (ref "P36") (pin "1") (pinfunction "1_1") (pintype "passive"))
      (node (ref "P5") (pin "1") (pinfunction "1_1") (pintype "passive"))
      (node (ref "P7") (pin "1") (pinfunction "1_1") (pintype "passive"))
      (node (ref "P8") (pin "1") (pinfunction "1_1") (pintype "passive"))
      (node (ref "P9") (pin "1") (pinfunction "1_1") (pintype "passive"))
      (node (ref "U1") (pin "8") (pinfunction "VDD/VREF_8") (pintype "power_in"))
      (node (ref "U2") (pin "1") (pinfunction "EXTVCC_1") (pintype "power_in"))
      (node (ref "U3") (pin "1") (pinfunction "EXTVCC_1") (pintype "power_in"))
      (node (ref "U4") (pin "1") (pinfunction "EXTVCC_1") (pintype "power_in"))
    )
    (net (code "2") (name "+12") (class "Default")
      (node (ref "F4") (pin "2") (pinfunction "2_2") (pintype "passive"))
      (node (ref "F7") (pin "2") (pinfunction "2_2") (pintype "passive"))
      (node (ref "K1") (pin "4") (pinfunction "4_4") (pintype "passive"))
      (node (ref "K2") (pin "4") (pinfunction "4_4") (pintype "passive"))
      (node (ref "K3") (pin "4") (pinfunction "4_4") (pintype "passive"))
      (node (ref "P37") (pin "1") (pinfunction "1_1") (pintype "passive"))
      (node (ref "P38") (pin "1") (pinfunction "1_1") (pintype "passive"))
      (node (ref "P39") (pin "1") (pinfunction "1_1") (pintype "passive"))
      (node (ref "P40") (pin "1") (pinfunction "1_1") (pintype "passive"))
      (node (ref "Q4") (pin "1") (pinfunction "D_1") (pintype "passive"))
      (node (ref "Q7") (pin "1") (pinfunction "D_1") (pintype "passive"))
      (node (ref "Q9") (pin "1") (pinfunction "D_1") (pintype "passive"))
    )
    (net (code "3") (name "/12V0_RELAY_TO_DC_MOTOR_1") (class "Default")
      (node (ref "F9") (pin "2") (pinfunction "2_2") (pintype "passive"))
      (node (ref "P17") (pin "1") (pinfunction "1_1") (pintype "passive"))
    )
    (net (code "4") (name "/12V0_RELAY_TO_DC_MOTOR_2") (class "Default")
      (node (ref "F10") (pin "2") (pinfunction "2_2") (pintype "passive"))
      (node (ref "P18") (pin "1") (pinfunction "1_1") (pintype "passive"))
    )
    (net (code "5") (name "/12V0_RELAY_TO_DC_MOTOR_3") (class "Default")
      (node (ref "F11") (pin "2") (pinfunction "2_2") (pintype "passive"))
      (node (ref "P19") (pin "1") (pinfunction "1_1") (pintype "passive"))
    )
    (net (code "6") (name "/12V0_RELAY_TO_DC_MOTOR_4") (class "Default")
      (node (ref "F12") (pin "2") (pinfunction "2_2") (pintype "passive"))
      (node (ref "P20") (pin "1") (pinfunction "1_1") (pintype "passive"))
    )
    (net (code "8") (name "/BATT_CONNN") (class "Default")
      (node (ref "P21") (pin "2") (pinfunction "2_2") (pintype "passive"))
      (node (ref "S1") (pin "2") (pinfunction "2_2") (pintype "passive"))
    )
    (net (code "9") (name "/BG_5V") (class "Default")
      (node (ref "Q2") (pin "2") (pinfunction "G_2") (pintype "passive"))
      (node (ref "U2") (pin "10") (pinfunction "BG_10") (pintype "output"))
    )
    (net (code "10") (name "/BG_12V_1") (class "Default")
      (node (ref "Q5") (pin "2") (pinfunction "G_2") (pintype "passive"))
      (node (ref "U3") (pin "10") (pinfunction "BG_10") (pintype "output"))
    )
    (net (code "11") (name "/BG_12V_2") (class "Default")
      (node (ref "Q8") (pin "2") (pinfunction "G_2") (pintype "passive"))
      (node (ref "U4") (pin "10") (pinfunction "BG_10") (pintype "output"))
    )
    (net (code "12") (name "/BOOST_5V") (class "Default")
      (node (ref "C1") (pin "2") (pinfunction "2_2") (pintype "passive"))
      (node (ref "D2") (pin "2") (pinfunction "K_2") (pintype "passive"))
      (node (ref "U2") (pin "12") (pinfunction "BOOST_12") (pintype "passive"))
    )
    (net (code "13") (name "/BOOST_12V_1") (class "Default")
      (node (ref "C7") (pin "1") (pinfunction "1_1") (pintype "passive"))
      (node (ref "D3") (pin "2") (pinfunction "K_2") (pintype "passive"))
      (node (ref "U3") (pin "12") (pinfunction "BOOST_12") (pintype "passive"))
    )
    (net (code "14") (name "/BOOST_12V_2") (class "Default")
      (node (ref "C21") (pin "1") (pinfunction "1_1") (pintype "passive"))
      (node (ref "D5") (pin "2") (pinfunction "K_2") (pintype "passive"))
      (node (ref "U4") (pin "12") (pinfunction "BOOST_12") (pintype "passive"))
    )
    (net (code "15") (name "/CH0") (class "Default")
      (node (ref "C5") (pin "2") (pinfunction "2_2") (pintype "passive"))
      (node (ref "R1") (pin "2") (pinfunction "2_2") (pintype "passive"))
      (node (ref "U1") (pin "2") (pinfunction "CH0_2") (pintype "input"))
    )
    (net (code "16") (name "/CLK") (class "Default")
      (node (ref "P1") (pin "1") (pinfunction "1_1") (pintype "passive"))
      (node (ref "R18") (pin "2") (pinfunction "2_2") (pintype "passive"))
    )
    (net (code "17") (name "/CNTRL_DC_MOTOR_RELAY") (class "Default")
      (node (ref "P23") (pin "2") (pinfunction "2_2") (pintype "passive"))
      (node (ref "Q9") (pin "2") (pinfunction "G_2") (pintype "passive"))
    )
    (net (code "18") (name "/CNTRL_STEP_RELAY") (class "Default")
      (node (ref "P22") (pin "1") (pinfunction "1_1") (pintype "passive"))
      (node (ref "Q7") (pin "2") (pinfunction "G_2") (pintype "passive"))
    )
    (net (code "19") (name "/CNTRL_VACUUM_RELAY") (class "Default")
      (node (ref "P22") (pin "2") (pinfunction "2_2") (pintype "passive"))
      (node (ref "Q4") (pin "2") (pinfunction "G_2") (pintype "passive"))
    )
    (net (code "20") (name "/COMP_5V") (class "Default")
      (node (ref "C15") (pin "1") (pinfunction "1_1") (pintype "passive"))
      (node (ref "C16") (pin "1") (pinfunction "1_1") (pintype "passive"))
      (node (ref "R3") (pin "1") (pinfunction "1_1") (pintype "passive"))
    )
    (net (code "21") (name "/COMP_12V_1") (class "Default")
      (node (ref "C12") (pin "1") (pinfunction "1_1") (pintype "passive"))
      (node (ref "C30") (pin "1") (pinfunction "1_1") (pintype "passive"))
      (node (ref "R2") (pin "1") (pinfunction "1_1") (pintype "passive"))
    )
    (net (code "22") (name "/COMP_12V_2") (class "Default")
      (node (ref "C27") (pin "2") (pinfunction "2_2") (pintype "passive"))
      (node (ref "C37") (pin "2") (pinfunction "2_2") (pintype "passive"))
      (node (ref "R5") (pin "1") (pinfunction "1_1") (pintype "passive"))
    )
    (net (code "23") (name "/DC_MOTOR_COIL") (class "Default")
      (node (ref "K3") (pin "1") (pinfunction "1_1") (pintype "passive"))
      (node (ref "Q9") (pin "3") (pinfunction "S_3") (pintype "passive"))
      (node (ref "R7") (pin "2") (pinfunction "2_2") (pintype "passive"))
    )
    (net (code "24") (name "/DC_MOTOR_RLY_TO_FUSE") (class "Default")
      (node (ref "F10") (pin "1") (pinfunction "1_1") (pintype "passive"))
      (node (ref "F11") (pin "1") (pinfunction "1_1") (pintype "passive"))
      (node (ref "F12") (pin "1") (pinfunction "1_1") (pintype "passive"))
      (node (ref "F9") (pin "1") (pinfunction "1_1") (pintype "passive"))
      (node (ref "K3") (pin "2") (pinfunction "2_2") (pintype "passive"))
    )
    (net (code "25") (name "/DIN") (class "Default")
      (node (ref "P27") (pin "1") (pinfunction "1_1") (pintype "passive"))
      (node (ref "R9") (pin "2") (pinfunction "2_2") (pintype "passive"))
    )
    (net (code "26") (name "/DOUT") (class "Default")
      (node (ref "P27") (pin "2") (pinfunction "2_2") (pintype "passive"))
      (node (ref "R8") (pin "2") (pinfunction "2_2") (pintype "passive"))
    )
    (net (code "27") (name "/INTVCC_5V") (class "Default")
      (node (ref "C17") (pin "1") (pinfunction "1_1") (pintype "passive"))
      (node (ref "D2") (pin "1") (pinfunction "A_1") (pintype "passive"))
      (node (ref "D2") (pin "3") (pinfunction "A_3") (pintype "passive"))
      (node (ref "U2") (pin "11") (pinfunction "INTVCC_11") (pintype "power_in"))
      (node (ref "U2") (pin "4") (pinfunction "FCB_4") (pintype "input"))
      (node (ref "U2") (pin "8") (pinfunction "VPROG_8") (pintype "input"))
    )
    (net (code "28") (name "/INTVCC_12V_1") (class "Default")
      (node (ref "C19") (pin "1") (pinfunction "1_1") (pintype "passive"))
      (node (ref "D3") (pin "1") (pinfunction "A_1") (pintype "passive"))
      (node (ref "D3") (pin "3") (pinfunction "A_3") (pintype "passive"))
      (node (ref "U3") (pin "11") (pinfunction "INTVCC_11") (pintype "power_in"))
      (node (ref "U3") (pin "4") (pinfunction "FCB_4") (pintype "input"))
    )
    (net (code "29") (name "/INTVCC_12V_2") (class "Default")
      (node (ref "C28") (pin "2") (pinfunction "2_2") (pintype "passive"))
      (node (ref "D5") (pin "1") (pinfunction "A_1") (pintype "passive"))
      (node (ref "D5") (pin "3") (pinfunction "A_3") (pintype "passive"))
      (node (ref "U4") (pin "11") (pinfunction "INTVCC_11") (pintype "power_in"))
      (node (ref "U4") (pin "4") (pinfunction "FCB_4") (pintype "input"))
    )
    (net (code "32") (name "/P12V0_RELAY_TO_STEPPER1") (class "Default")
      (node (ref "F6") (pin "2") (pinfunction "2_2") (pintype "passive"))
      (node (ref "P15") (pin "1") (pinfunction "1_1") (pintype "passive"))
    )
    (net (code "33") (name "/P12V0_RELAY_TO_STEPPER2") (class "Default")
      (node (ref "F8") (pin "2") (pinfunction "2_2") (pintype "passive"))
      (node (ref "P16") (pin "1") (pinfunction "1_1") (pintype "passive"))
    )
    (net (code "34") (name "/P12V0_RELAY_TO_VACUUM") (class "Default")
      (node (ref "F5") (pin "2") (pinfunction "2_2") (pintype "passive"))
      (node (ref "P14") (pin "1") (pinfunction "1_1") (pintype "passive"))
    )
    (net (code "35") (name "/RC_FILTER") (class "Default")
      (node (ref "R1") (pin "1") (pinfunction "1_1") (pintype "passive"))
      (node (ref "R10") (pin "1") (pinfunction "1_1") (pintype "passive"))
      (node (ref "R17") (pin "2") (pinfunction "2_2") (pintype "passive"))
    )
    (net (code "36") (name "/SS_5V") (class "Default")
      (node (ref "C13") (pin "2") (pinfunction "2_2") (pintype "passive"))
      (node (ref "U2") (pin "3") (pinfunction "RUN/SS_3") (pintype "input"))
    )
    (net (code "37") (name "/SS_12V_1") (class "Default")
      (node (ref "C9") (pin "2") (pinfunction "2_2") (pintype "passive"))
      (node (ref "U3") (pin "3") (pinfunction "RUN/SS_3") (pintype "input"))
    )
    (net (code "38") (name "/SS_12V_2") (class "Default")
      (node (ref "C24") (pin "2") (pinfunction "2_2") (pintype "passive"))
      (node (ref "U4") (pin "3") (pinfunction "RUN/SS_3") (pintype "input"))
    )
    (net (code "39") (name "/STEPPER_COIL") (class "Default")
      (node (ref "K2") (pin "1") (pinfunction "1_1") (pintype "passive"))
      (node (ref "Q7") (pin "3") (pinfunction "S_3") (pintype "passive"))
      (node (ref "R6") (pin "2") (pinfunction "2_2") (pintype "passive"))
    )
    (net (code "40") (name "/STEPPER_RLY_TO_FUSE") (class "Default")
      (node (ref "F6") (pin "1") (pinfunction "1_1") (pintype "passive"))
      (node (ref "F8") (pin "1") (pinfunction "1_1") (pintype "passive"))
      (node (ref "K2") (pin "2") (pinfunction "2_2") (pintype "passive"))
    )
    (net (code "41") (name "/SW_5V") (class "Default")
      (node (ref "C1") (pin "1") (pinfunction "1_1") (pintype "passive"))
      (node (ref "D1") (pin "2") (pinfunction "K_2") (pintype "passive"))
      (node (ref "L1") (pin "1") (pinfunction "1_1") (pintype "passive"))
      (node (ref "Q1") (pin "3") (pinfunction "S_3") (pintype "passive"))
      (node (ref "Q2") (pin "1") (pinfunction "D_1") (pintype "passive"))
      (node (ref "U2") (pin "14") (pinfunction "SW_14") (pintype "passive"))
    )
    (net (code "42") (name "/SW_12V_1") (class "Default")
      (node (ref "C7") (pin "2") (pinfunction "2_2") (pintype "passive"))
      (node (ref "D4") (pin "2") (pinfunction "K_2") (pintype "passive"))
      (node (ref "L2") (pin "1") (pinfunction "1_1") (pintype "passive"))
      (node (ref "Q3") (pin "3") (pinfunction "S_3") (pintype "passive"))
      (node (ref "Q5") (pin "1") (pinfunction "D_1") (pintype "passive"))
      (node (ref "U3") (pin "14") (pinfunction "SW_14") (pintype "passive"))
    )
    (net (code "43") (name "/SW_12V_2") (class "Default")
      (node (ref "C21") (pin "2") (pinfunction "2_2") (pintype "passive"))
      (node (ref "D6") (pin "2") (pinfunction "K_2") (pintype "passive"))
      (node (ref "L3") (pin "1") (pinfunction "1_1") (pintype "passive"))
      (node (ref "Q6") (pin "3") (pinfunction "S_3") (pintype "passive"))
      (node (ref "Q8") (pin "1") (pinfunction "D_1") (pintype "passive"))
      (node (ref "U4") (pin "14") (pinfunction "SW_14") (pintype "passive"))
    )
    (net (code "44") (name "/TG_5V") (class "Default")
      (node (ref "Q1") (pin "2") (pinfunction "G_2") (pintype "passive"))
      (node (ref "U2") (pin "13") (pinfunction "TG_13") (pintype "output"))
    )
    (net (code "45") (name "/TG_12V_1") (class "Default")
      (node (ref "Q3") (pin "2") (pinfunction "G_2") (pintype "passive"))
      (node (ref "U3") (pin "13") (pinfunction "TG_13") (pintype "output"))
    )
    (net (code "46") (name "/TG_12V_2") (class "Default")
      (node (ref "Q6") (pin "2") (pinfunction "G_2") (pintype "passive"))
      (node (ref "U4") (pin "13") (pinfunction "TG_13") (pintype "output"))
    )
    (net (code "47") (name "/VACUUM_COIL") (class "Default")
      (node (ref "K1") (pin "1") (pinfunction "1_1") (pintype "passive"))
      (node (ref "Q4") (pin "3") (pinfunction "S_3") (pintype "passive"))
      (node (ref "R4") (pin "2") (pinfunction "2_2") (pintype "passive"))
    )
    (net (code "48") (name "/VACUUM_RLY_TO_FUSE") (class "Default")
      (node (ref "F5") (pin "1") (pinfunction "1_1") (pintype "passive"))
      (node (ref "K1") (pin "2") (pinfunction "2_2") (pintype "passive"))
    )
    (net (code "49") (name "/VOSENSE_12V_1") (class "Default")
      (node (ref "R12") (pin "1") (pinfunction "1_1") (pintype "passive"))
      (node (ref "R13") (pin "2") (pinfunction "2_2") (pintype "passive"))
      (node (ref "U3") (pin "7") (pinfunction "VOSENSE_7") (pintype "input"))
    )
    (net (code "50") (name "/VOSENSE_12V_2") (class "Default")
      (node (ref "R15") (pin "1") (pinfunction "1_1") (pintype "passive"))
      (node (ref "R16") (pin "2") (pinfunction "2_2") (pintype "passive"))
      (node (ref "U4") (pin "7") (pinfunction "VOSENSE_7") (pintype "input"))
    )
    (net (code "51") (name "/VOUT_5V") (class "Default")
      (node (ref "C11") (pin "2") (pinfunction "A_2") (pintype "passive"))
      (node (ref "C14") (pin "2") (pinfunction "A_2") (pintype "passive"))
      (node (ref "C6") (pin "1") (pinfunction "1_1") (pintype "passive"))
      (node (ref "F1") (pin "1") (pinfunction "1_1") (pintype "passive"))
      (node (ref "L1") (pin "2") (pinfunction "2_2") (pintype "passive"))
      (node (ref "U2") (pin "7") (pinfunction "VOSENSE_7") (pintype "input"))
    )
    (net (code "52") (name "/VOUT_12V_1") (class "Default")
      (node (ref "C20") (pin "1") (pinfunction "1_1") (pintype "passive"))
      (node (ref "C22") (pin "2") (pinfunction "A_2") (pintype "passive"))
      (node (ref "C23") (pin "2") (pinfunction "A_2") (pintype "passive"))
      (node (ref "F4") (pin "1") (pinfunction "1_1") (pintype "passive"))
      (node (ref "L2") (pin "2") (pinfunction "2_2") (pintype "passive"))
      (node (ref "R20") (pin "2") (pinfunction "2_2") (pintype "passive"))
    )
    (net (code "53") (name "/VOUT_12V_2") (class "Default")
      (node (ref "C25") (pin "1") (pinfunction "1_1") (pintype "passive"))
      (node (ref "C26") (pin "2") (pinfunction "A_2") (pintype "passive"))
      (node (ref "C29") (pin "2") (pinfunction "A_2") (pintype "passive"))
      (node (ref "F7") (pin "1") (pinfunction "1_1") (pintype "passive"))
      (node (ref "L3") (pin "2") (pinfunction "2_2") (pintype "passive"))
      (node (ref "R14") (pin "2") (pinfunction "2_2") (pintype "passive"))
    )
    (net (code "54") (name "/~{CS}") (class "Default")
      (node (ref "P1") (pin "2") (pinfunction "2_2") (pintype "passive"))
      (node (ref "R11") (pin "2") (pinfunction "2_2") (pintype "passive"))
    )
    (net (code "55") (name "GND") (class "Default")
      (node (ref "C10") (pin "2") (pinfunction "2_2") (pintype "passive"))
      (node (ref "C11") (pin "1") (pinfunction "C_1") (pintype "passive"))
      (node (ref "C12") (pin "2") (pinfunction "2_2") (pintype "passive"))
      (node (ref "C13") (pin "1") (pinfunction "1_1") (pintype "passive"))
      (node (ref "C14") (pin "1") (pinfunction "C_1") (pintype "passive"))
      (node (ref "C15") (pin "2") (pinfunction "2_2") (pintype "passive"))
      (node (ref "C16") (pin "2") (pinfunction "2_2") (pintype "passive"))
      (node (ref "C17") (pin "2") (pinfunction "2_2") (pintype "passive"))
      (node (ref "C18") (pin "1") (pinfunction "C_1") (pintype "passive"))
      (node (ref "C19") (pin "2") (pinfunction "2_2") (pintype "passive"))
      (node (ref "C2") (pin "2") (pinfunction "2_2") (pintype "passive"))
      (node (ref "C20") (pin "2") (pinfunction "2_2") (pintype "passive"))
      (node (ref "C22") (pin "1") (pinfunction "C_1") (pintype "passive"))
      (node (ref "C23") (pin "1") (pinfunction "C_1") (pintype "passive"))
      (node (ref "C24") (pin "1") (pinfunction "1_1") (pintype "passive"))
      (node (ref "C25") (pin "2") (pinfunction "2_2") (pintype "passive"))
      (node (ref "C26") (pin "1") (pinfunction "C_1") (pintype "passive"))
      (node (ref "C27") (pin "1") (pinfunction "1_1") (pintype "passive"))
      (node (ref "C28") (pin "1") (pinfunction "1_1") (pintype "passive"))
      (node (ref "C29") (pin "1") (pinfunction "C_1") (pintype "passive"))
      (node (ref "C3") (pin "1") (pinfunction "C_1") (pintype "passive"))
      (node (ref "C30") (pin "2") (pinfunction "2_2") (pintype "passive"))
      (node (ref "C31") (pin "2") (pinfunction "2_2") (pintype "passive"))
      (node (ref "C32") (pin "1") (pinfunction "C_1") (pintype "passive"))
      (node (ref "C33") (pin "1") (pinfunction "C_1") (pintype "passive"))
      (node (ref "C34") (pin "1") (pinfunction "C_1") (pintype "passive"))
      (node (ref "C35") (pin "1") (pinfunction "1_1") (pintype "passive"))
      (node (ref "C37") (pin "1") (pinfunction "1_1") (pintype "passive"))
      (node (ref "C4") (pin "1") (pinfunction "C_1") (pintype "passive"))
      (node (ref "C5") (pin "1") (pinfunction "1_1") (pintype "passive"))
      (node (ref "C6") (pin "2") (pinfunction "2_2") (pintype "passive"))
      (node (ref "C8") (pin "1") (pinfunction "C_1") (pintype "passive"))
      (node (ref "C9") (pin "1") (pinfunction "1_1") (pintype "passive"))
      (node (ref "D1") (pin "1") (pinfunction "A_1") (pintype "passive"))
      (node (ref "D1") (pin "3") (pinfunction "A_3") (pintype "passive"))
      (node (ref "D4") (pin "1") (pinfunction "A_1") (pintype "passive"))
      (node (ref "D4") (pin "3") (pinfunction "A_3") (pintype "passive"))
      (node (ref "D6") (pin "1") (pinfunction "A_1") (pintype "passive"))
      (node (ref "D6") (pin "3") (pinfunction "A_3") (pintype "passive"))
      (node (ref "K1") (pin "3") (pinfunction "3_3") (pintype "passive"))
      (node (ref "K2") (pin "3") (pinfunction "3_3") (pintype "passive"))
      (node (ref "K3") (pin "3") (pinfunction "3_3") (pintype "passive"))
      (node (ref "MH1") (pin "1") (pinfunction "1_1") (pintype "passive"))
      (node (ref "MH2") (pin "1") (pinfunction "1_1") (pintype "passive"))
      (node (ref "MH3") (pin "1") (pinfunction "1_1") (pintype "passive"))
      (node (ref "MH4") (pin "1") (pinfunction "1_1") (pintype "passive"))
      (node (ref "MH5") (pin "1") (pinfunction "1_1") (pintype "passive"))
      (node (ref "MH6") (pin "1") (pinfunction "1_1") (pintype "passive"))
      (node (ref "P10") (pin "2") (pinfunction "2_2") (pintype "passive"))
      (node (ref "P11") (pin "2") (pinfunction "2_2") (pintype "passive"))
      (node (ref "P12") (pin "2") (pinfunction "2_2") (pintype "passive"))
      (node (ref "P13") (pin "2") (pinfunction "2_2") (pintype "passive"))
      (node (ref "P14") (pin "2") (pinfunction "2_2") (pintype "passive"))
      (node (ref "P15") (pin "2") (pinfunction "2_2") (pintype "passive"))
      (node (ref "P16") (pin "2") (pinfunction "2_2") (pintype "passive"))
      (node (ref "P17") (pin "2") (pinfunction "2_2") (pintype "passive"))
      (node (ref "P18") (pin "2") (pinfunction "2_2") (pintype "passive"))
      (node (ref "P19") (pin "2") (pinfunction "2_2") (pintype "passive"))
      (node (ref "P2") (pin "2") (pinfunction "2_2") (pintype "passive"))
      (node (ref "P20") (pin "2") (pinfunction "2_2") (pintype "passive"))
      (node (ref "P21") (pin "1") (pinfunction "1_1") (pintype "passive"))
      (node (ref "P24") (pin "1") (pinfunction "1_1") (pintype "passive"))
      (node (ref "P24") (pin "2") (pinfunction "2_2") (pintype "passive"))
      (node (ref "P25") (pin "1") (pinfunction "1_1") (pintype "passive"))
      (node (ref "P25") (pin "2") (pinfunction "2_2") (pintype "passive"))
      (node (ref "P26") (pin "1") (pinfunction "1_1") (pintype "passive"))
      (node (ref "P26") (pin "2") (pinfunction "2_2") (pintype "passive"))
      (node (ref "P28") (pin "2") (pinfunction "2_2") (pintype "passive"))
      (node (ref "P29") (pin "2") (pinfunction "2_2") (pintype "passive"))
      (node (ref "P3") (pin "2") (pinfunction "2_2") (pintype "passive"))
      (node (ref "P30") (pin "2") (pinfunction "2_2") (pintype "passive"))
      (node (ref "P31") (pin "2") (pinfunction "2_2") (pintype "passive"))
      (node (ref "P32") (pin "2") (pinfunction "2_2") (pintype "passive"))
      (node (ref "P33") (pin "2") (pinfunction "2_2") (pintype "passive"))
      (node (ref "P34") (pin "2") (pinfunction "2_2") (pintype "passive"))
      (node (ref "P35") (pin "2") (pinfunction "2_2") (pintype "passive"))
      (node (ref "P36") (pin "2") (pinfunction "2_2") (pintype "passive"))
      (node (ref "P37") (pin "2") (pinfunction "2_2") (pintype "passive"))
      (node (ref "P38") (pin "2") (pinfunction "2_2") (pintype "passive"))
      (node (ref "P39") (pin "2") (pinfunction "2_2") (pintype "passive"))
      (node (ref "P4") (pin "2") (pinfunction "2_2") (pintype "passive"))
      (node (ref "P40") (pin "2") (pinfunction "2_2") (pintype "passive"))
      (node (ref "P5") (pin "2") (pinfunction "2_2") (pintype "passive"))
      (node (ref "P6") (pin "2") (pinfunction "2_2") (pintype "passive"))
      (node (ref "P7") (pin "2") (pinfunction "2_2") (pintype "passive"))
      (node (ref "P8") (pin "2") (pinfunction "2_2") (pintype "passive"))
      (node (ref "P9") (pin "2") (pinfunction "2_2") (pintype "passive"))
      (node (ref "Q2") (pin "3") (pinfunction "S_3") (pintype "passive"))
      (node (ref "Q5") (pin "3") (pinfunction "S_3") (pintype "passive"))
      (node (ref "Q8") (pin "3") (pinfunction "S_3") (pintype "passive"))
      (node (ref "R13") (pin "1") (pinfunction "1_1") (pintype "passive"))
      (node (ref "R16") (pin "1") (pinfunction "1_1") (pintype "passive"))
      (node (ref "R17") (pin "1") (pinfunction "1_1") (pintype "passive"))
      (node (ref "R4") (pin "1") (pinfunction "1_1") (pintype "passive"))
      (node (ref "R6") (pin "1") (pinfunction "1_1") (pintype "passive"))
      (node (ref "R7") (pin "1") (pinfunction "1_1") (pintype "passive"))
      (node (ref "U1") (pin "3") (pinfunction "CH1_3") (pintype "input"))
      (node (ref "U1") (pin "4") (pinfunction "VSS_4") (pintype "power_in"))
      (node (ref "U2") (pin "6") (pinfunction "SGND_6") (pintype "power_in"))
      (node (ref "U2") (pin "9") (pinfunction "PGND_9") (pintype "power_in"))
      (node (ref "U3") (pin "6") (pinfunction "SGND_6") (pintype "power_in"))
      (node (ref "U3") (pin "9") (pinfunction "PGND_9") (pintype "power_in"))
      (node (ref "U4") (pin "6") (pinfunction "SGND_6") (pintype "power_in"))
      (node (ref "U4") (pin "9") (pinfunction "PGND_9") (pintype "power_in"))
    )
    (net (code "56") (name "Net-(F2-Pad2)") (class "Default")
      (node (ref "F2") (pin "2") (pinfunction "2_2") (pintype "passive"))
      (node (ref "P4") (pin "1") (pinfunction "1_1") (pintype "passive"))
    )
    (net (code "57") (name "Net-(F3-Pad2)") (class "Default")
      (node (ref "F3") (pin "2") (pinfunction "2_2") (pintype "passive"))
      (node (ref "P6") (pin "1") (pinfunction "1_1") (pintype "passive"))
    )
    (net (code "58") (name "Net-(R12-Pad2)") (class "Default")
      (node (ref "R12") (pin "2") (pinfunction "2_2") (pintype "passive"))
      (node (ref "R20") (pin "1") (pinfunction "1_1") (pintype "passive"))
    )
    (net (code "59") (name "Net-(R14-Pad1)") (class "Default")
      (node (ref "R14") (pin "1") (pinfunction "1_1") (pintype "passive"))
      (node (ref "R15") (pin "2") (pinfunction "2_2") (pintype "passive"))
    )
    (net (code "60") (name "Net-(U1-CLK)") (class "Default")
      (node (ref "R18") (pin "1") (pinfunction "1_1") (pintype "passive"))
      (node (ref "U1") (pin "7") (pinfunction "CLK_7") (pintype "input"))
    )
    (net (code "61") (name "Net-(U1-DIN)") (class "Default")
      (node (ref "R9") (pin "1") (pinfunction "1_1") (pintype "passive"))
      (node (ref "U1") (pin "5") (pinfunction "DIN_5") (pintype "input"))
    )
    (net (code "62") (name "Net-(U1-DOUT)") (class "Default")
      (node (ref "R8") (pin "1") (pinfunction "1_1") (pintype "passive"))
      (node (ref "U1") (pin "6") (pinfunction "DOUT_6") (pintype "tri_state"))
    )
    (net (code "63") (name "Net-(U1-~{CS}{slash}SHDN)") (class "Default")
      (node (ref "R11") (pin "1") (pinfunction "1_1") (pintype "passive"))
      (node (ref "U1") (pin "1") (pinfunction "~{CS}/SHDN_1") (pintype "input"))
    )
    (net (code "64") (name "Net-(U2-ITH)") (class "Default")
      (node (ref "R3") (pin "2") (pinfunction "2_2") (pintype "passive"))
      (node (ref "U2") (pin "5") (pinfunction "ITH_5") (pintype "passive"))
    )
    (net (code "65") (name "Net-(U3-ITH)") (class "Default")
      (node (ref "R2") (pin "2") (pinfunction "2_2") (pintype "passive"))
      (node (ref "U3") (pin "5") (pinfunction "ITH_5") (pintype "passive"))
    )
    (net (code "66") (name "Net-(U4-ITH)") (class "Default")
      (node (ref "R5") (pin "2") (pinfunction "2_2") (pintype "passive"))
      (node (ref "U4") (pin "5") (pinfunction "ITH_5") (pintype "passive"))
    )
    (net (code "67") (name "PP_VBATT") (class "Default")
      (node (ref "C10") (pin "1") (pinfunction "1_1") (pintype "passive"))
      (node (ref "C18") (pin "2") (pinfunction "A_2") (pintype "passive"))
      (node (ref "C2") (pin "1") (pinfunction "1_1") (pintype "passive"))
      (node (ref "C3") (pin "2") (pinfunction "A_2") (pintype "passive"))
      (node (ref "C31") (pin "1") (pinfunction "1_1") (pintype "passive"))
      (node (ref "C32") (pin "2") (pinfunction "A_2") (pintype "passive"))
      (node (ref "C33") (pin "2") (pinfunction "A_2") (pintype "passive"))
      (node (ref "C34") (pin "2") (pinfunction "A_2") (pintype "passive"))
      (node (ref "C4") (pin "2") (pinfunction "A_2") (pintype "passive"))
      (node (ref "C8") (pin "2") (pinfunction "A_2") (pintype "passive"))
      (node (ref "Q1") (pin "1") (pinfunction "D_1") (pintype "passive"))
      (node (ref "Q3") (pin "1") (pinfunction "D_1") (pintype "passive"))
      (node (ref "Q6") (pin "1") (pinfunction "D_1") (pintype "passive"))
      (node (ref "R10") (pin "2") (pinfunction "2_2") (pintype "passive"))
      (node (ref "S1") (pin "1") (pinfunction "1_1") (pintype "passive"))
      (node (ref "U2") (pin "15") (pinfunction "TK_15") (pintype "input"))
      (node (ref "U2") (pin "16") (pinfunction "VIN_16") (pintype "power_in"))
      (node (ref "U3") (pin "15") (pinfunction "TK_15") (pintype "input"))
      (node (ref "U3") (pin "16") (pinfunction "VIN_16") (pintype "power_in"))
      (node (ref "U4") (pin "15") (pinfunction "TK_15") (pintype "input"))
      (node (ref "U4") (pin "16") (pinfunction "VIN_16") (pintype "power_in"))
    )
    (net (code "68") (name "unconnected-(P23-Pad1)") (class "Default")
      (node (ref "P23") (pin "1") (pinfunction "1_1") (pintype "passive+no_connect"))
    )
    (net (code "69") (name "unconnected-(U2-SYNC-Pad2)") (class "Default")
      (node (ref "U2") (pin "2") (pinfunction "SYNC_2") (pintype "input+no_connect"))
    )
    (net (code "70") (name "unconnected-(U3-SYNC-Pad2)") (class "Default")
      (node (ref "U3") (pin "2") (pinfunction "SYNC_2") (pintype "input+no_connect"))
    )
    (net (code "71") (name "unconnected-(U3-VPROG-Pad8)") (class "Default")
      (node (ref "U3") (pin "8") (pinfunction "VPROG_8") (pintype "input+no_connect"))
    )
    (net (code "72") (name "unconnected-(U4-SYNC-Pad2)") (class "Default")
      (node (ref "U4") (pin "2") (pinfunction "SYNC_2") (pintype "input+no_connect"))
    )
    (net (code "73") (name "unconnected-(U4-VPROG-Pad8)") (class "Default")
      (node (ref "U4") (pin "8") (pinfunction "VPROG_8") (pintype "input+no_connect"))
    )
  )
)
